# axiom_beta_sensor_cmv12000_v0_13_9164f85.net
KiCad netlist of a schematic drawn in EAGLE
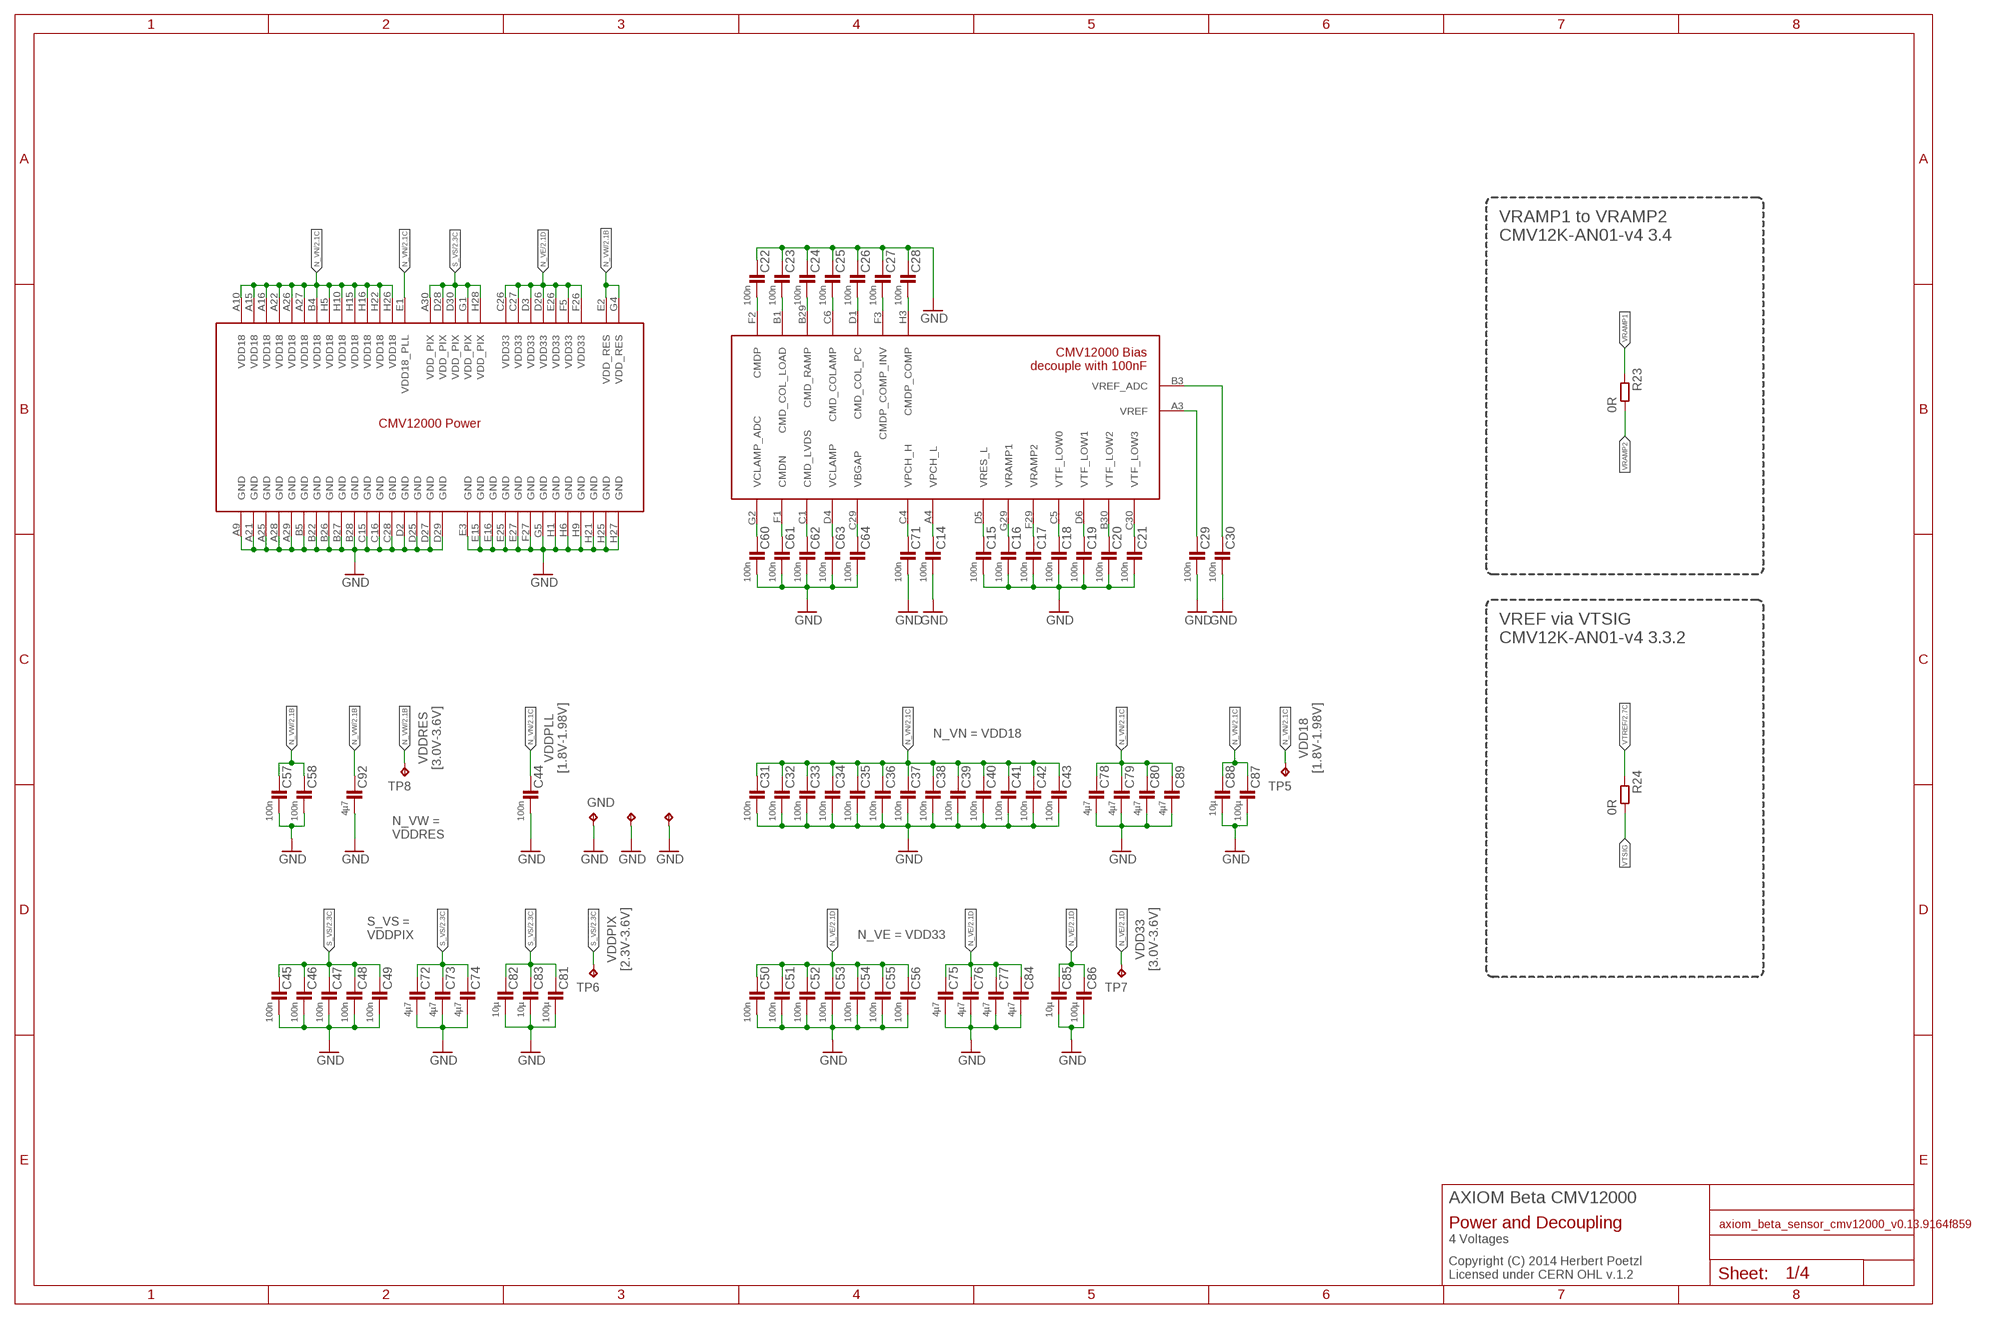
[diagram p0: schematic, sheet 1]
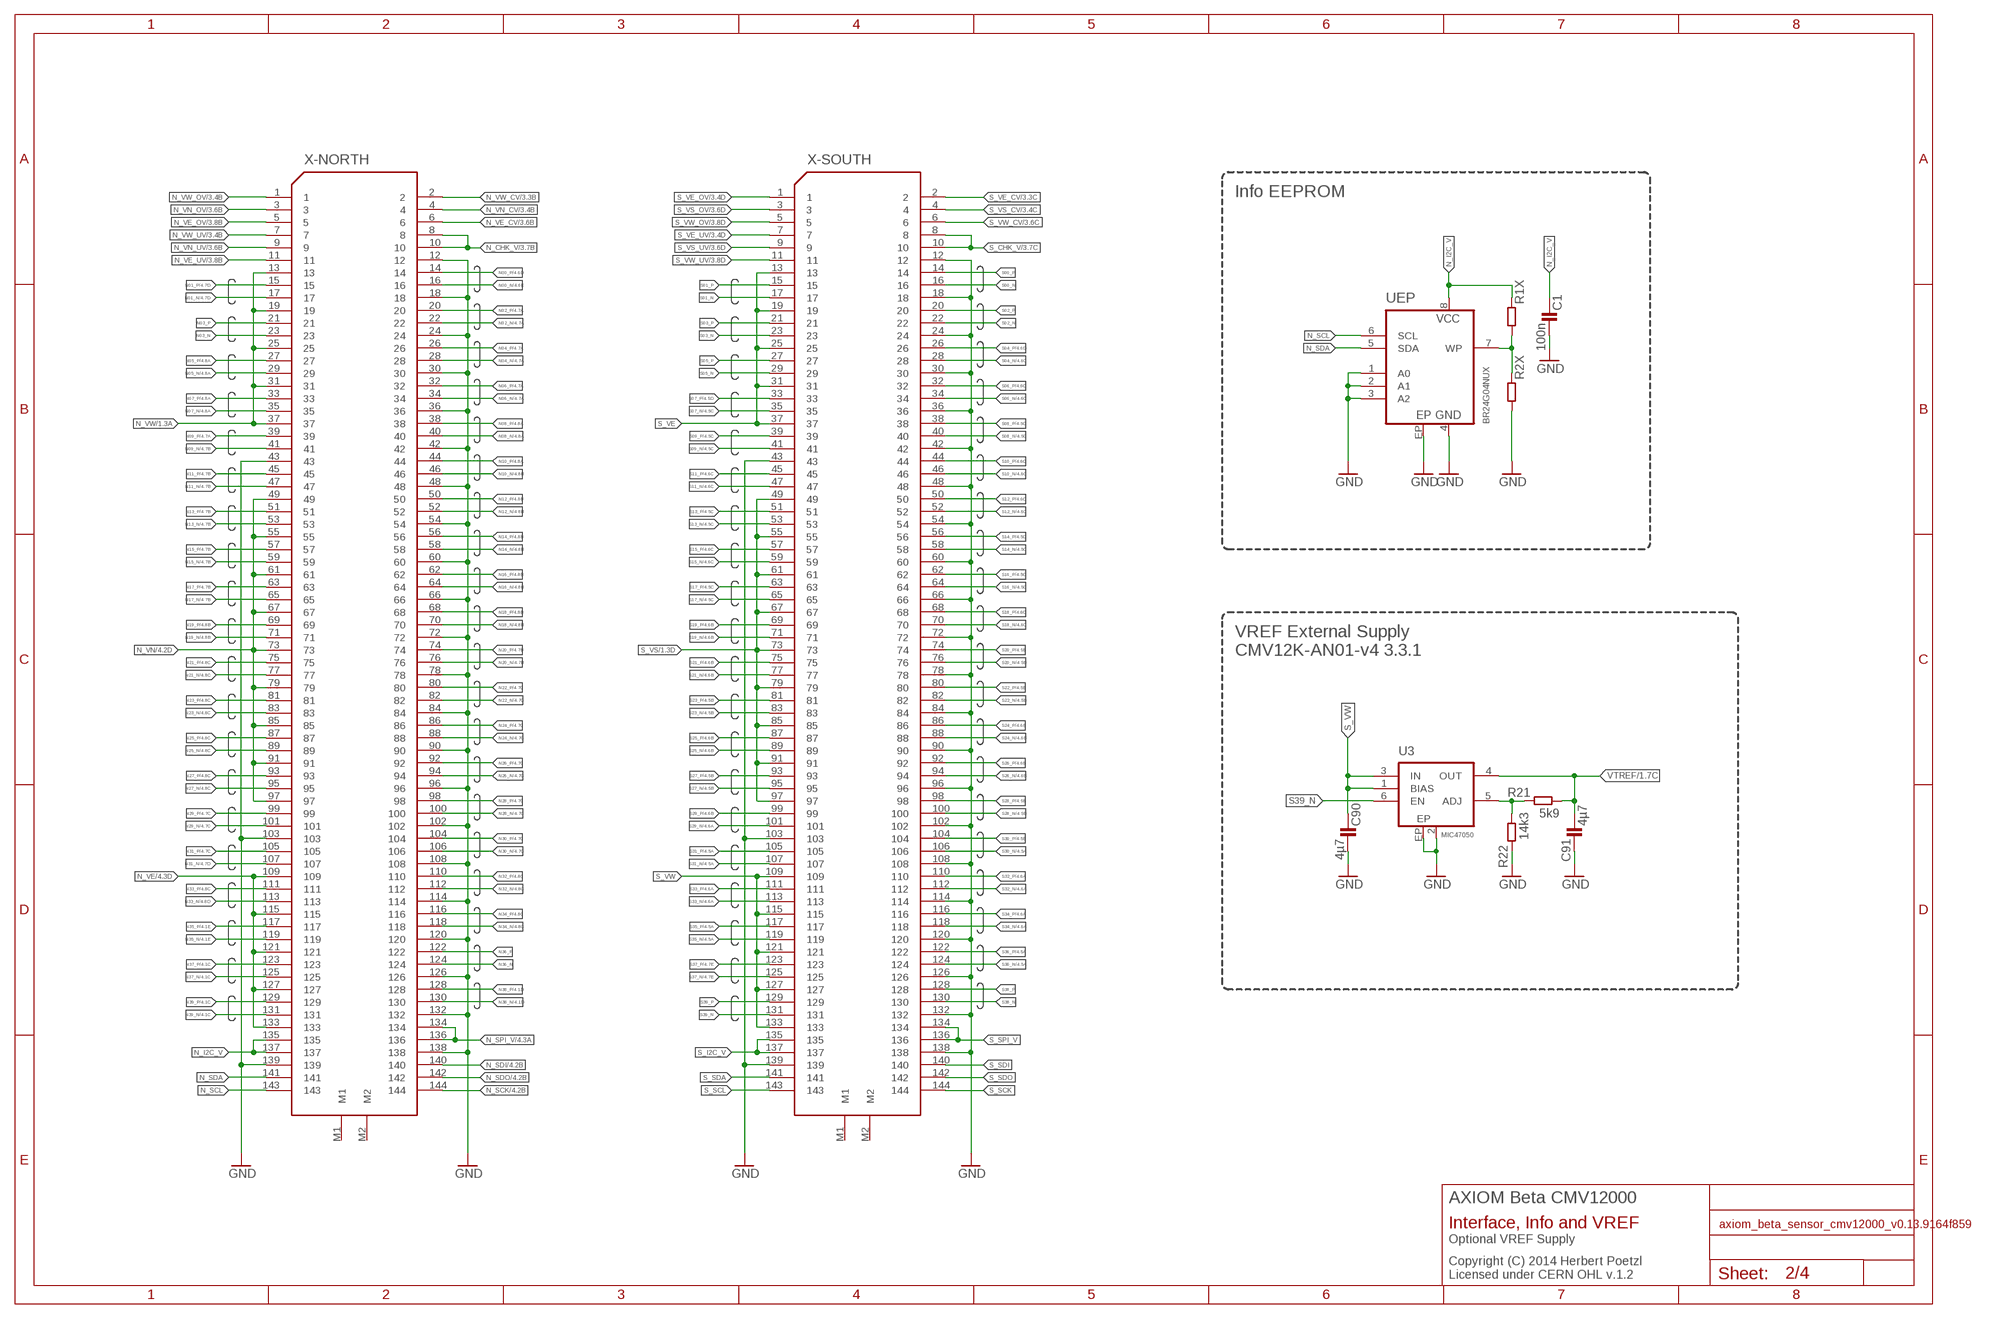
[diagram p1: schematic, sheet 2]
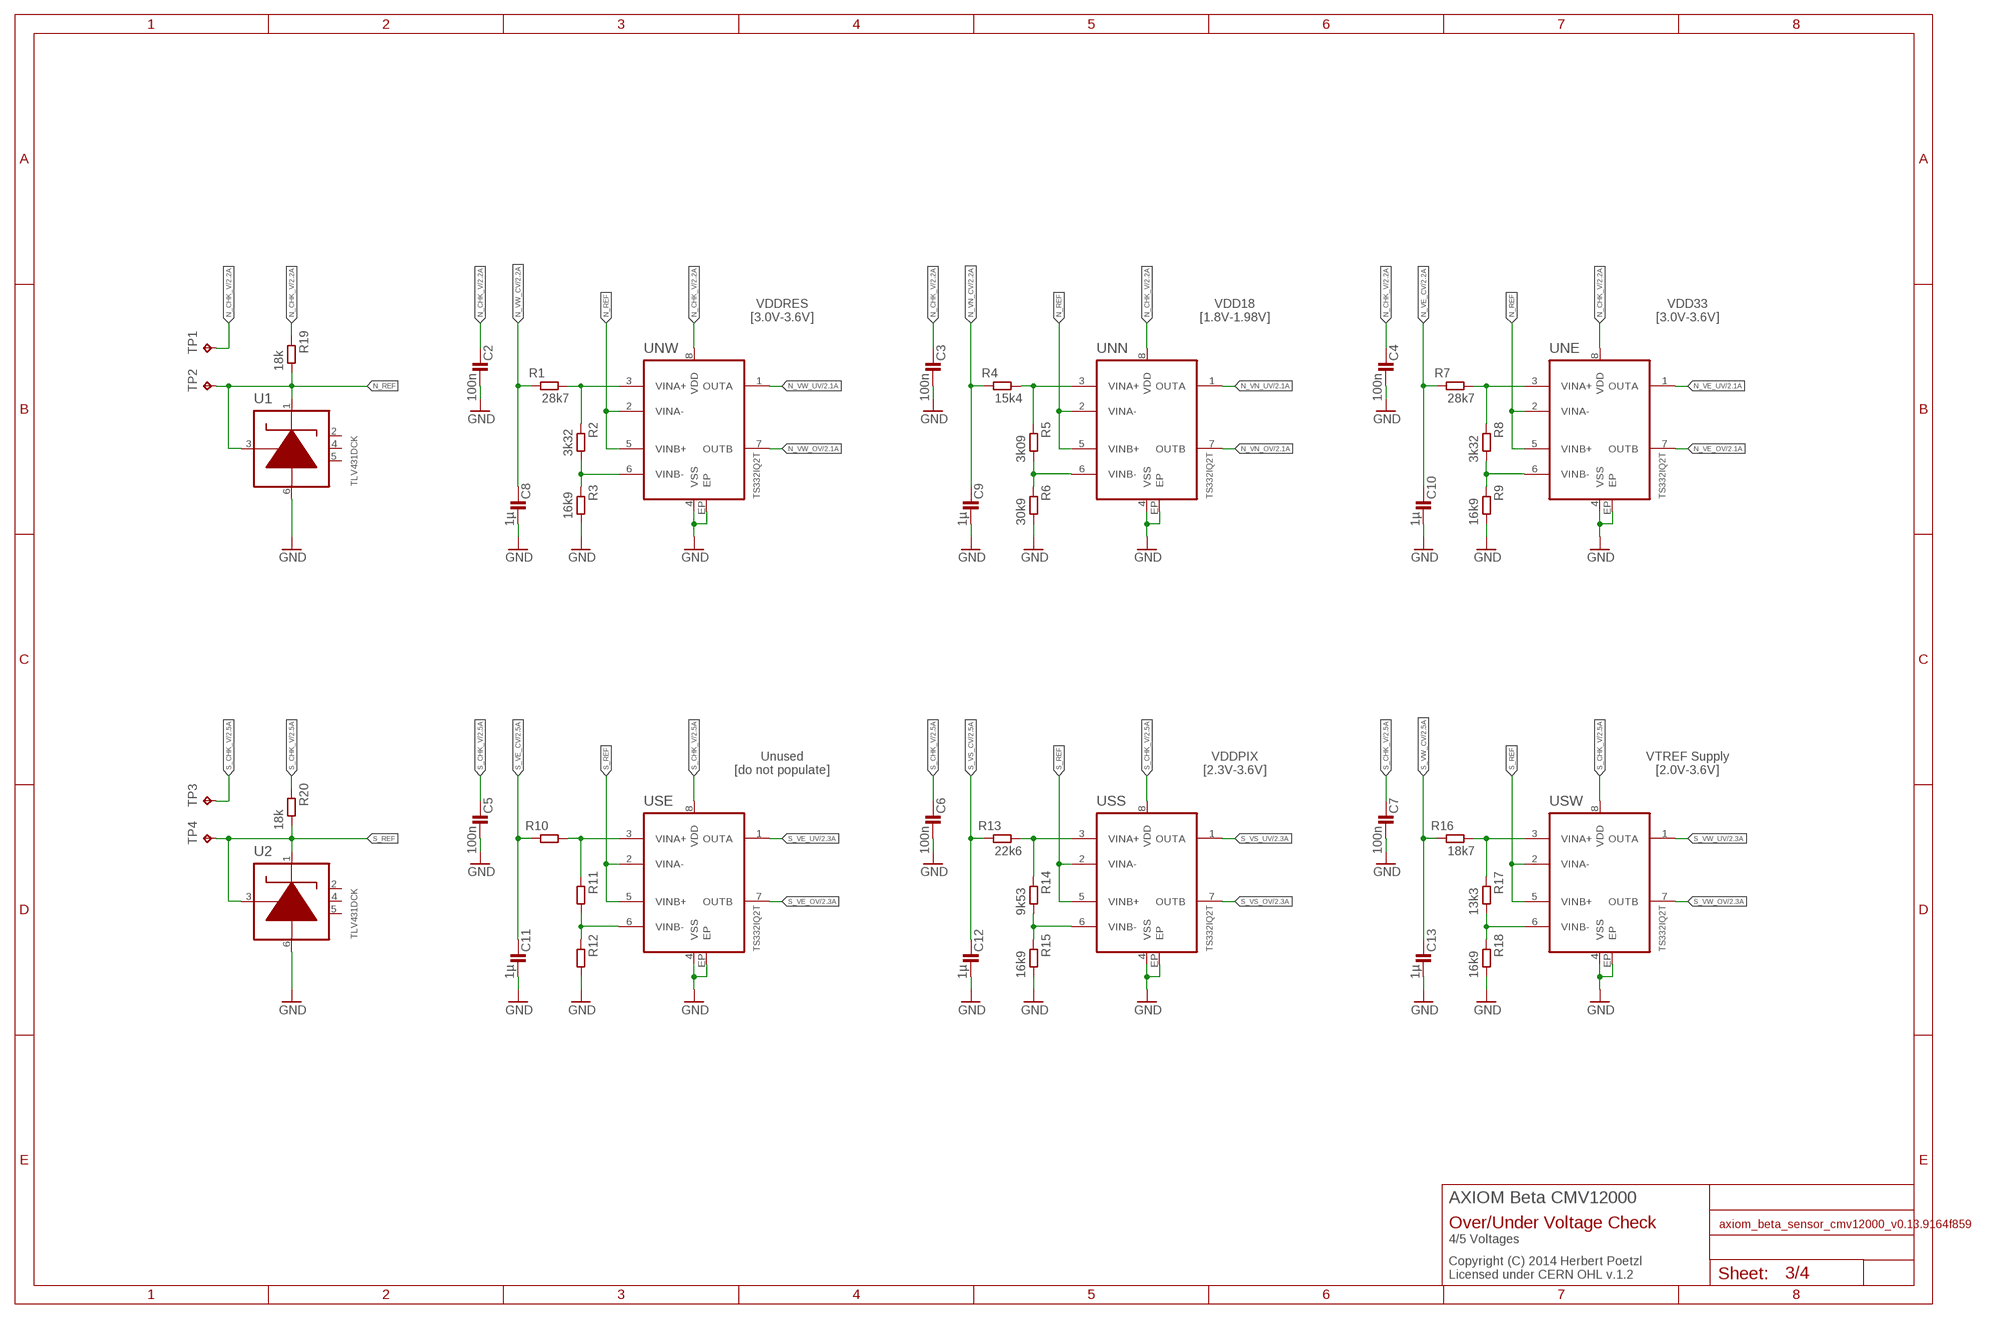
[diagram p2: schematic, sheet 3]
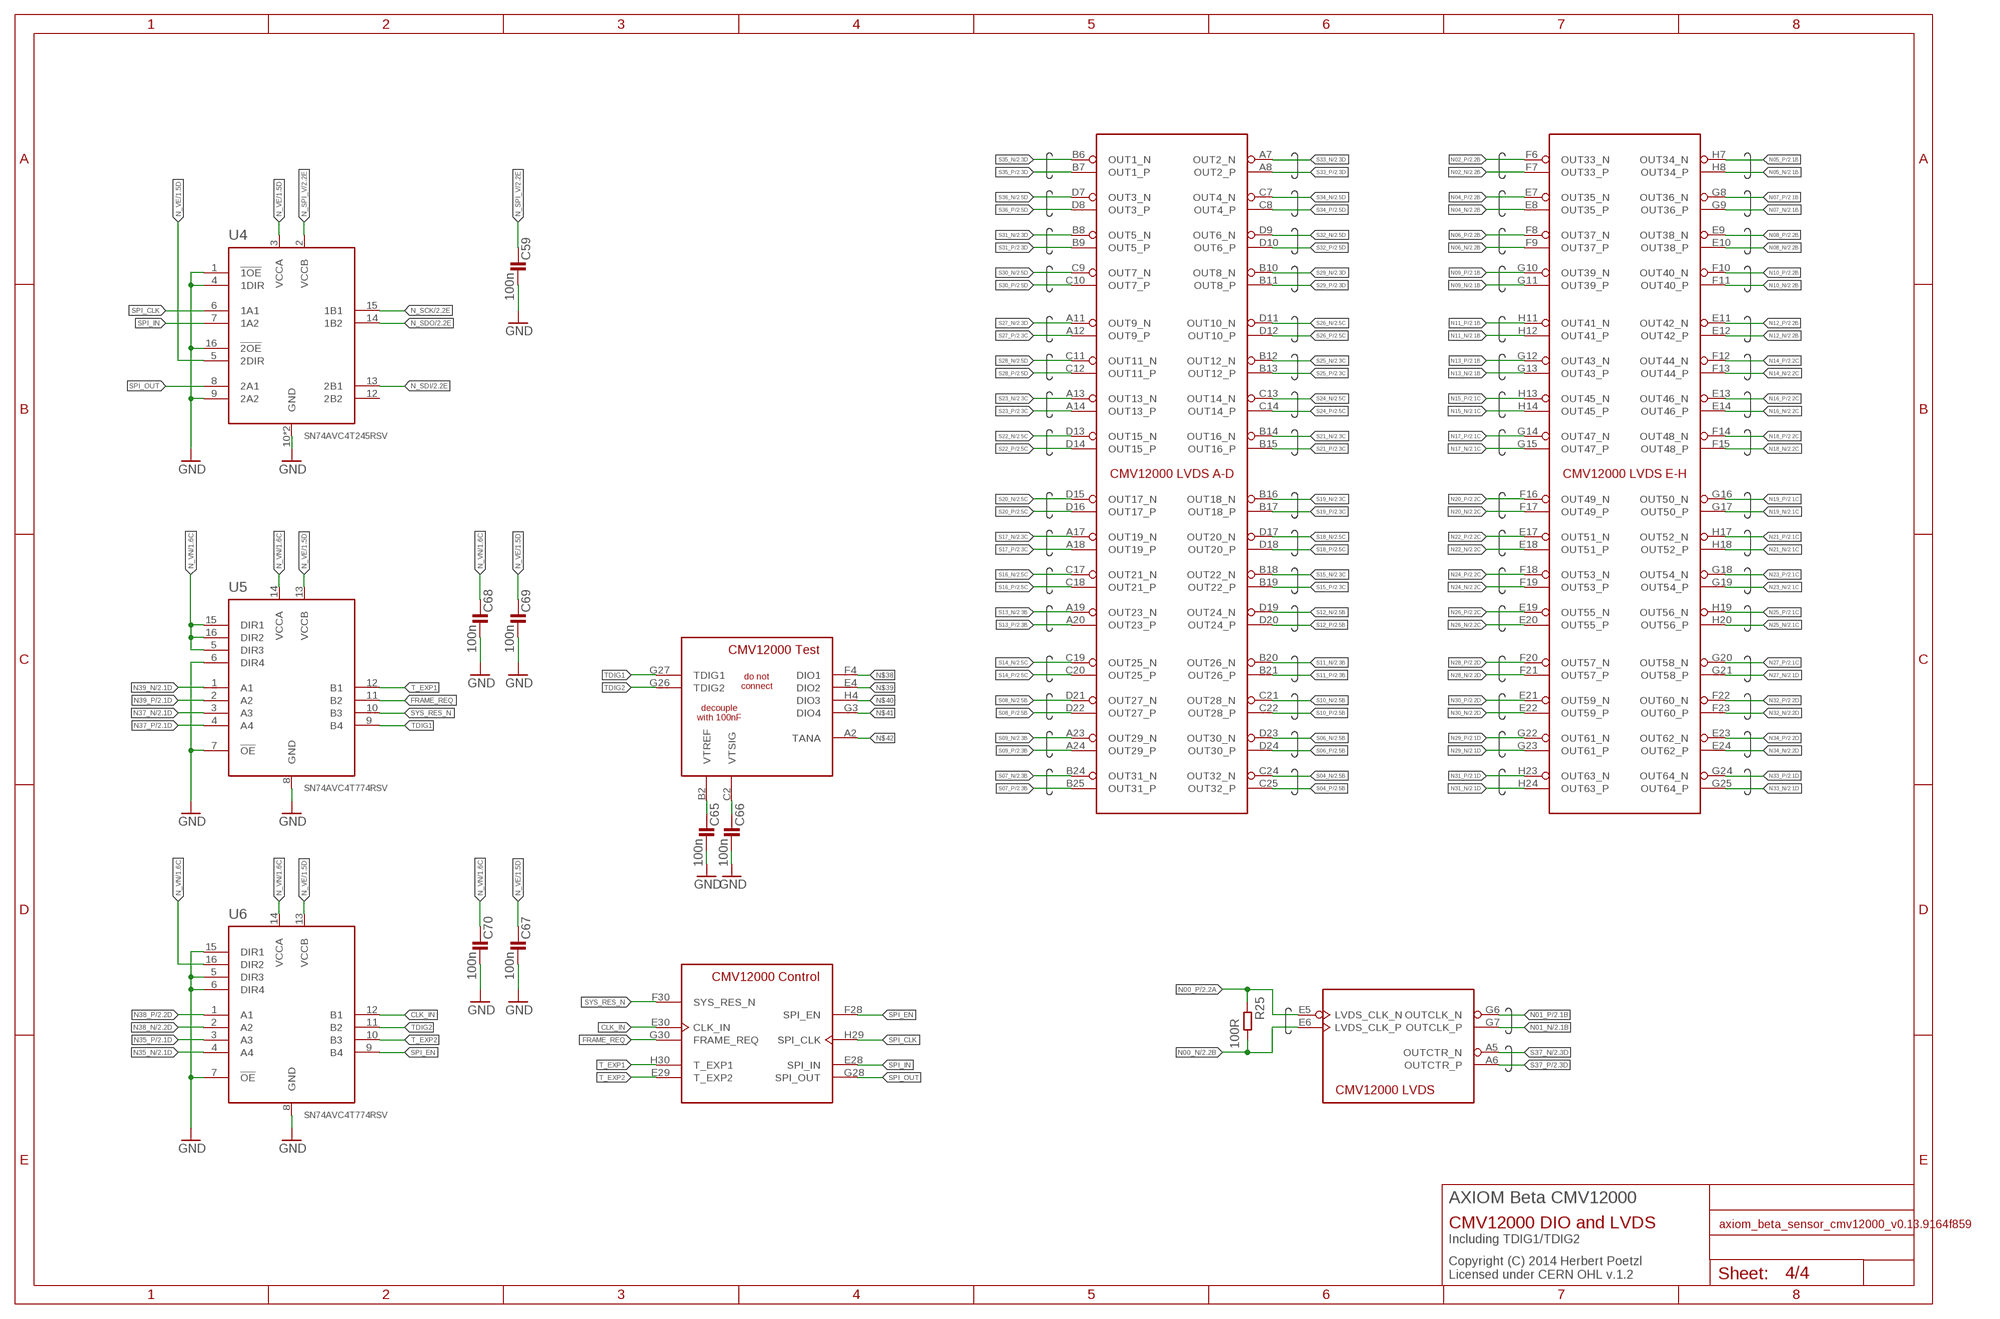
[diagram p3: schematic, sheet 4]

(export (version "E")
  (design (tool "Eeschema 10.0.6"))
  (components
    (comp (ref "C2")
      (value "100n")
      (footprint "eagle-import:0402-C")
      (libsource (lib "eagle-import") (part "C0402-C"))
    )
    (comp (ref "C3")
      (value "100n")
      (footprint "eagle-import:0402-C")
      (libsource (lib "eagle-import") (part "C0402-C"))
    )
    (comp (ref "C4")
      (value "100n")
      (footprint "eagle-import:0402-C")
      (libsource (lib "eagle-import") (part "C0402-C"))
    )
    (comp (ref "C5")
      (value "100n")
      (footprint "eagle-import:0402-C")
      (libsource (lib "eagle-import") (part "C0402-C"))
    )
    (comp (ref "C6")
      (value "100n")
      (footprint "eagle-import:0402-C")
      (libsource (lib "eagle-import") (part "C0402-C"))
    )
    (comp (ref "C7")
      (value "100n")
      (footprint "eagle-import:0402-C")
      (libsource (lib "eagle-import") (part "C0402-C"))
    )
    (comp (ref "C8")
      (value "1µ")
      (footprint "eagle-import:0402-C")
      (libsource (lib "eagle-import") (part "C0402-C"))
    )
    (comp (ref "C9")
      (value "1µ")
      (footprint "eagle-import:0402-C")
      (libsource (lib "eagle-import") (part "C0402-C"))
    )
    (comp (ref "C10")
      (value "1µ")
      (footprint "eagle-import:0402-C")
      (libsource (lib "eagle-import") (part "C0402-C"))
    )
    (comp (ref "C11")
      (value "1µ")
      (footprint "eagle-import:0402-C")
      (libsource (lib "eagle-import") (part "C0402-C"))
    )
    (comp (ref "C12")
      (value "1µ")
      (footprint "eagle-import:0402-C")
      (libsource (lib "eagle-import") (part "C0402-C"))
    )
    (comp (ref "C13")
      (value "1µ")
      (footprint "eagle-import:0402-C")
      (libsource (lib "eagle-import") (part "C0402-C"))
    )
    (comp (ref "R1")
      (value "28k7")
      (footprint "eagle-import:0402-C")
      (libsource (lib "eagle-import") (part "R0402-C"))
    )
    (comp (ref "R2")
      (value "3k32")
      (footprint "eagle-import:0402-C")
      (libsource (lib "eagle-import") (part "R0402-C"))
    )
    (comp (ref "R3")
      (value "16k9")
      (footprint "eagle-import:0402-C")
      (libsource (lib "eagle-import") (part "R0402-C"))
    )
    (comp (ref "R4")
      (value "15k4")
      (footprint "eagle-import:0402-C")
      (libsource (lib "eagle-import") (part "R0402-C"))
    )
    (comp (ref "R5")
      (value "3k09")
      (footprint "eagle-import:0402-C")
      (libsource (lib "eagle-import") (part "R0402-C"))
    )
    (comp (ref "R6")
      (value "30k9")
      (footprint "eagle-import:0402-C")
      (libsource (lib "eagle-import") (part "R0402-C"))
    )
    (comp (ref "R7")
      (value "28k7")
      (footprint "eagle-import:0402-C")
      (libsource (lib "eagle-import") (part "R0402-C"))
    )
    (comp (ref "R8")
      (value "3k32")
      (footprint "eagle-import:0402-C")
      (libsource (lib "eagle-import") (part "R0402-C"))
    )
    (comp (ref "R9")
      (value "16k9")
      (footprint "eagle-import:0402-C")
      (libsource (lib "eagle-import") (part "R0402-C"))
    )
    (comp (ref "R10")
      (value "R0402-C")
      (footprint "eagle-import:0402-C")
      (libsource (lib "eagle-import") (part "R0402-C"))
    )
    (comp (ref "R11")
      (value "R0402-C")
      (footprint "eagle-import:0402-C")
      (libsource (lib "eagle-import") (part "R0402-C"))
    )
    (comp (ref "R12")
      (value "R0402-C")
      (footprint "eagle-import:0402-C")
      (libsource (lib "eagle-import") (part "R0402-C"))
    )
    (comp (ref "R13")
      (value "22k6")
      (footprint "eagle-import:0402-C")
      (libsource (lib "eagle-import") (part "R0402-C"))
    )
    (comp (ref "R14")
      (value "9k53")
      (footprint "eagle-import:0402-C")
      (libsource (lib "eagle-import") (part "R0402-C"))
    )
    (comp (ref "R15")
      (value "16k9")
      (footprint "eagle-import:0402-C")
      (libsource (lib "eagle-import") (part "R0402-C"))
    )
    (comp (ref "R16")
      (value "18k7")
      (footprint "eagle-import:0402-C")
      (libsource (lib "eagle-import") (part "R0402-C"))
    )
    (comp (ref "R17")
      (value "13k3")
      (footprint "eagle-import:0402-C")
      (libsource (lib "eagle-import") (part "R0402-C"))
    )
    (comp (ref "R18")
      (value "16k9")
      (footprint "eagle-import:0402-C")
      (libsource (lib "eagle-import") (part "R0402-C"))
    )
    (comp (ref "R19")
      (value "18k")
      (footprint "eagle-import:0402-C")
      (libsource (lib "eagle-import") (part "R0402-C"))
    )
    (comp (ref "R20")
      (value "18k")
      (footprint "eagle-import:0402-C")
      (libsource (lib "eagle-import") (part "R0402-C"))
    )
    (comp (ref "TP1")
      (value "TPTP10R")
      (footprint "eagle-import:TP10R")
      (libsource (lib "eagle-import") (part "TPTP10R"))
    )
    (comp (ref "TP2")
      (value "TPTP10R")
      (footprint "eagle-import:TP10R")
      (libsource (lib "eagle-import") (part "TPTP10R"))
    )
    (comp (ref "TP3")
      (value "TPTP10R")
      (footprint "eagle-import:TP10R")
      (libsource (lib "eagle-import") (part "TPTP10R"))
    )
    (comp (ref "TP4")
      (value "TPTP10R")
      (footprint "eagle-import:TP10R")
      (libsource (lib "eagle-import") (part "TPTP10R"))
    )
    (comp (ref "U1")
      (value "TLV431DCK")
      (footprint "eagle-import:SOT65P210X110-6N")
      (libsource (lib "eagle-import") (part "TLV431DCK"))
    )
    (comp (ref "U2")
      (value "TLV431DCK")
      (footprint "eagle-import:SOT65P210X110-6N")
      (libsource (lib "eagle-import") (part "TLV431DCK"))
    )
    (comp (ref "UNE")
      (value "TS332IQ2T")
      (footprint "eagle-import:DFN200X200X100-9N")
      (libsource (lib "eagle-import") (part "TS332IQ2T"))
    )
    (comp (ref "UNN")
      (value "TS332IQ2T")
      (footprint "eagle-import:DFN200X200X100-9N")
      (libsource (lib "eagle-import") (part "TS332IQ2T"))
    )
    (comp (ref "UNW")
      (value "TS332IQ2T")
      (footprint "eagle-import:DFN200X200X100-9N")
      (libsource (lib "eagle-import") (part "TS332IQ2T"))
    )
    (comp (ref "USE")
      (value "TS332IQ2T")
      (footprint "eagle-import:DFN200X200X100-9N")
      (libsource (lib "eagle-import") (part "TS332IQ2T"))
    )
    (comp (ref "USS")
      (value "TS332IQ2T")
      (footprint "eagle-import:DFN200X200X100-9N")
      (libsource (lib "eagle-import") (part "TS332IQ2T"))
    )
    (comp (ref "USW")
      (value "TS332IQ2T")
      (footprint "eagle-import:DFN200X200X100-9N")
      (libsource (lib "eagle-import") (part "TS332IQ2T"))
    )
    (comp (ref "C59")
      (value "100n")
      (footprint "eagle-import:0402-C")
      (libsource (lib "eagle-import") (part "C0402-C"))
    )
    (comp (ref "C65")
      (value "100n")
      (footprint "eagle-import:0402-C")
      (libsource (lib "eagle-import") (part "C0402-C"))
    )
    (comp (ref "C66")
      (value "100n")
      (footprint "eagle-import:0402-C")
      (libsource (lib "eagle-import") (part "C0402-C"))
    )
    (comp (ref "C67")
      (value "100n")
      (footprint "eagle-import:0402-C")
      (libsource (lib "eagle-import") (part "C0402-C"))
    )
    (comp (ref "C68")
      (value "100n")
      (footprint "eagle-import:0402-C")
      (libsource (lib "eagle-import") (part "C0402-C"))
    )
    (comp (ref "C69")
      (value "100n")
      (footprint "eagle-import:0402-C")
      (libsource (lib "eagle-import") (part "C0402-C"))
    )
    (comp (ref "C70")
      (value "100n")
      (footprint "eagle-import:0402-C")
      (libsource (lib "eagle-import") (part "C0402-C"))
    )
    (comp (ref "R25")
      (value "100R")
      (footprint "eagle-import:0402-C")
      (libsource (lib "eagle-import") (part "R0402-C"))
    )
    (comp (ref "SENSOR")
      (value "CMV12000ANDON")
      (footprint "eagle-import:10-30-07-237-400T4")
      (libsource (lib "eagle-import") (part "CMV12000ANDON"))
    )
    (comp (ref "U4")
      (value "SN74AVC4T245RSV")
      (footprint "eagle-import:QFN40P185X265X55-16N")
      (libsource (lib "eagle-import") (part "SN74AVC4T245RSV"))
    )
    (comp (ref "U5")
      (value "SN74AVC4T774RSV")
      (footprint "eagle-import:QFN40P185X265X55-16N")
      (libsource (lib "eagle-import") (part "SN74AVC4T774RSV"))
    )
    (comp (ref "U6")
      (value "SN74AVC4T774RSV")
      (footprint "eagle-import:QFN40P185X265X55-16N")
      (libsource (lib "eagle-import") (part "SN74AVC4T774RSV"))
    )
    (comp (ref "C14")
      (value "100n")
      (footprint "eagle-import:0402-C")
      (libsource (lib "eagle-import") (part "C0402-C"))
    )
    (comp (ref "C15")
      (value "100n")
      (footprint "eagle-import:0402-C")
      (libsource (lib "eagle-import") (part "C0402-C"))
    )
    (comp (ref "C16")
      (value "100n")
      (footprint "eagle-import:0402-C")
      (libsource (lib "eagle-import") (part "C0402-C"))
    )
    (comp (ref "C17")
      (value "100n")
      (footprint "eagle-import:0402-C")
      (libsource (lib "eagle-import") (part "C0402-C"))
    )
    (comp (ref "C18")
      (value "100n")
      (footprint "eagle-import:0402-C")
      (libsource (lib "eagle-import") (part "C0402-C"))
    )
    (comp (ref "C19")
      (value "100n")
      (footprint "eagle-import:0402-C")
      (libsource (lib "eagle-import") (part "C0402-C"))
    )
    (comp (ref "C20")
      (value "100n")
      (footprint "eagle-import:0402-C")
      (libsource (lib "eagle-import") (part "C0402-C"))
    )
    (comp (ref "C21")
      (value "100n")
      (footprint "eagle-import:0402-C")
      (libsource (lib "eagle-import") (part "C0402-C"))
    )
    (comp (ref "C22")
      (value "100n")
      (footprint "eagle-import:0402-C")
      (libsource (lib "eagle-import") (part "C0402-C"))
    )
    (comp (ref "C23")
      (value "100n")
      (footprint "eagle-import:0402-C")
      (libsource (lib "eagle-import") (part "C0402-C"))
    )
    (comp (ref "C24")
      (value "100n")
      (footprint "eagle-import:0402-C")
      (libsource (lib "eagle-import") (part "C0402-C"))
    )
    (comp (ref "C25")
      (value "100n")
      (footprint "eagle-import:0402-C")
      (libsource (lib "eagle-import") (part "C0402-C"))
    )
    (comp (ref "C26")
      (value "100n")
      (footprint "eagle-import:0402-C")
      (libsource (lib "eagle-import") (part "C0402-C"))
    )
    (comp (ref "C27")
      (value "100n")
      (footprint "eagle-import:0402-C")
      (libsource (lib "eagle-import") (part "C0402-C"))
    )
    (comp (ref "C28")
      (value "100n")
      (footprint "eagle-import:0402-C")
      (libsource (lib "eagle-import") (part "C0402-C"))
    )
    (comp (ref "C29")
      (value "100n")
      (footprint "eagle-import:0402-C")
      (libsource (lib "eagle-import") (part "C0402-C"))
    )
    (comp (ref "C30")
      (value "100n")
      (footprint "eagle-import:0402-C")
      (libsource (lib "eagle-import") (part "C0402-C"))
    )
    (comp (ref "C31")
      (value "100n")
      (footprint "eagle-import:0402-C")
      (libsource (lib "eagle-import") (part "C0402-C"))
    )
    (comp (ref "C32")
      (value "100n")
      (footprint "eagle-import:0402-C")
      (libsource (lib "eagle-import") (part "C0402-C"))
    )
    (comp (ref "C33")
      (value "100n")
      (footprint "eagle-import:0402-C")
      (libsource (lib "eagle-import") (part "C0402-C"))
    )
    (comp (ref "C34")
      (value "100n")
      (footprint "eagle-import:0402-C")
      (libsource (lib "eagle-import") (part "C0402-C"))
    )
    (comp (ref "C35")
      (value "100n")
      (footprint "eagle-import:0402-C")
      (libsource (lib "eagle-import") (part "C0402-C"))
    )
    (comp (ref "C36")
      (value "100n")
      (footprint "eagle-import:0402-C")
      (libsource (lib "eagle-import") (part "C0402-C"))
    )
    (comp (ref "C37")
      (value "100n")
      (footprint "eagle-import:0402-C")
      (libsource (lib "eagle-import") (part "C0402-C"))
    )
    (comp (ref "C38")
      (value "100n")
      (footprint "eagle-import:0402-C")
      (libsource (lib "eagle-import") (part "C0402-C"))
    )
    (comp (ref "C39")
      (value "100n")
      (footprint "eagle-import:0402-C")
      (libsource (lib "eagle-import") (part "C0402-C"))
    )
    (comp (ref "C40")
      (value "100n")
      (footprint "eagle-import:0402-C")
      (libsource (lib "eagle-import") (part "C0402-C"))
    )
    (comp (ref "C41")
      (value "100n")
      (footprint "eagle-import:0402-C")
      (libsource (lib "eagle-import") (part "C0402-C"))
    )
    (comp (ref "C42")
      (value "100n")
      (footprint "eagle-import:0402-C")
      (libsource (lib "eagle-import") (part "C0402-C"))
    )
    (comp (ref "C43")
      (value "100n")
      (footprint "eagle-import:0402-C")
      (libsource (lib "eagle-import") (part "C0402-C"))
    )
    (comp (ref "C44")
      (value "100n")
      (footprint "eagle-import:0402-C")
      (libsource (lib "eagle-import") (part "C0402-C"))
    )
    (comp (ref "C45")
      (value "100n")
      (footprint "eagle-import:0402-C")
      (libsource (lib "eagle-import") (part "C0402-C"))
    )
    (comp (ref "C46")
      (value "100n")
      (footprint "eagle-import:0402-C")
      (libsource (lib "eagle-import") (part "C0402-C"))
    )
    (comp (ref "C47")
      (value "100n")
      (footprint "eagle-import:0402-C")
      (libsource (lib "eagle-import") (part "C0402-C"))
    )
    (comp (ref "C48")
      (value "100n")
      (footprint "eagle-import:0402-C")
      (libsource (lib "eagle-import") (part "C0402-C"))
    )
    (comp (ref "C49")
      (value "100n")
      (footprint "eagle-import:0402-C")
      (libsource (lib "eagle-import") (part "C0402-C"))
    )
    (comp (ref "C50")
      (value "100n")
      (footprint "eagle-import:0402-C")
      (libsource (lib "eagle-import") (part "C0402-C"))
    )
    (comp (ref "C51")
      (value "100n")
      (footprint "eagle-import:0402-C")
      (libsource (lib "eagle-import") (part "C0402-C"))
    )
    (comp (ref "C52")
      (value "100n")
      (footprint "eagle-import:0402-C")
      (libsource (lib "eagle-import") (part "C0402-C"))
    )
    (comp (ref "C53")
      (value "100n")
      (footprint "eagle-import:0402-C")
      (libsource (lib "eagle-import") (part "C0402-C"))
    )
    (comp (ref "C54")
      (value "100n")
      (footprint "eagle-import:0402-C")
      (libsource (lib "eagle-import") (part "C0402-C"))
    )
    (comp (ref "C55")
      (value "100n")
      (footprint "eagle-import:0402-C")
      (libsource (lib "eagle-import") (part "C0402-C"))
    )
    (comp (ref "C56")
      (value "100n")
      (footprint "eagle-import:0402-C")
      (libsource (lib "eagle-import") (part "C0402-C"))
    )
    (comp (ref "C57")
      (value "100n")
      (footprint "eagle-import:0402-C")
      (libsource (lib "eagle-import") (part "C0402-C"))
    )
    (comp (ref "C58")
      (value "100n")
      (footprint "eagle-import:0402-C")
      (libsource (lib "eagle-import") (part "C0402-C"))
    )
    (comp (ref "C60")
      (value "100n")
      (footprint "eagle-import:0402-C")
      (libsource (lib "eagle-import") (part "C0402-C"))
    )
    (comp (ref "C61")
      (value "100n")
      (footprint "eagle-import:0402-C")
      (libsource (lib "eagle-import") (part "C0402-C"))
    )
    (comp (ref "C62")
      (value "100n")
      (footprint "eagle-import:0402-C")
      (libsource (lib "eagle-import") (part "C0402-C"))
    )
    (comp (ref "C63")
      (value "100n")
      (footprint "eagle-import:0402-C")
      (libsource (lib "eagle-import") (part "C0402-C"))
    )
    (comp (ref "C64")
      (value "100n")
      (footprint "eagle-import:0402-C")
      (libsource (lib "eagle-import") (part "C0402-C"))
    )
    (comp (ref "C71")
      (value "100n")
      (footprint "eagle-import:0402-C")
      (libsource (lib "eagle-import") (part "C0402-C"))
    )
    (comp (ref "C72")
      (value "4µ7")
      (footprint "eagle-import:0402-B")
      (libsource (lib "eagle-import") (part "C0402-B"))
    )
    (comp (ref "C73")
      (value "4µ7")
      (footprint "eagle-import:0402-C")
      (libsource (lib "eagle-import") (part "C0402-C"))
    )
    (comp (ref "C74")
      (value "4µ7")
      (footprint "eagle-import:0402-C")
      (libsource (lib "eagle-import") (part "C0402-C"))
    )
    (comp (ref "C75")
      (value "4µ7")
      (footprint "eagle-import:0402-C")
      (libsource (lib "eagle-import") (part "C0402-C"))
    )
    (comp (ref "C76")
      (value "4µ7")
      (footprint "eagle-import:0402-C")
      (libsource (lib "eagle-import") (part "C0402-C"))
    )
    (comp (ref "C77")
      (value "4µ7")
      (footprint "eagle-import:0402-B")
      (libsource (lib "eagle-import") (part "C0402-B"))
    )
    (comp (ref "C78")
      (value "4µ7")
      (footprint "eagle-import:0402-B")
      (libsource (lib "eagle-import") (part "C0402-B"))
    )
    (comp (ref "C79")
      (value "4µ7")
      (footprint "eagle-import:0402-C")
      (libsource (lib "eagle-import") (part "C0402-C"))
    )
    (comp (ref "C80")
      (value "4µ7")
      (footprint "eagle-import:0402-C")
      (libsource (lib "eagle-import") (part "C0402-C"))
    )
    (comp (ref "C81")
      (value "100µ")
      (footprint "eagle-import:1206-B")
      (libsource (lib "eagle-import") (part "C1206-B"))
    )
    (comp (ref "C82")
      (value "10µ")
      (footprint "eagle-import:0603-C")
      (libsource (lib "eagle-import") (part "C0603-C"))
    )
    (comp (ref "C83")
      (value "10µ")
      (footprint "eagle-import:0603-C")
      (libsource (lib "eagle-import") (part "C0603-C"))
    )
    (comp (ref "C84")
      (value "4µ7")
      (footprint "eagle-import:0402-C")
      (libsource (lib "eagle-import") (part "C0402-C"))
    )
    (comp (ref "C85")
      (value "10µ")
      (footprint "eagle-import:0603-C")
      (libsource (lib "eagle-import") (part "C0603-C"))
    )
    (comp (ref "C86")
      (value "100µ")
      (footprint "eagle-import:1206-B")
      (libsource (lib "eagle-import") (part "C1206-B"))
    )
    (comp (ref "C87")
      (value "100µ")
      (footprint "eagle-import:1206-B")
      (libsource (lib "eagle-import") (part "C1206-B"))
    )
    (comp (ref "C88")
      (value "10µ")
      (footprint "eagle-import:0603-C")
      (libsource (lib "eagle-import") (part "C0603-C"))
    )
    (comp (ref "C89")
      (value "4µ7")
      (footprint "eagle-import:0402-C")
      (libsource (lib "eagle-import") (part "C0402-C"))
    )
    (comp (ref "C92")
      (value "4µ7")
      (footprint "eagle-import:0402-C")
      (libsource (lib "eagle-import") (part "C0402-C"))
    )
    (comp (ref "GND")
      (value "TPTP10R")
      (footprint "eagle-import:TP10R")
      (libsource (lib "eagle-import") (part "TPTP10R"))
    )
    (comp (ref "GND75")
      (value "TPTP10R")
      (footprint "eagle-import:TP10R")
      (libsource (lib "eagle-import") (part "TPTP10R"))
    )
    (comp (ref "GND77")
      (value "TPTP10R")
      (footprint "eagle-import:TP10R")
      (libsource (lib "eagle-import") (part "TPTP10R"))
    )
    (comp (ref "R23")
      (value "0R")
      (footprint "eagle-import:0402-C")
      (libsource (lib "eagle-import") (part "R0402-C"))
    )
    (comp (ref "R24")
      (value "0R")
      (footprint "eagle-import:0402-C")
      (libsource (lib "eagle-import") (part "R0402-C"))
    )
    (comp (ref "TP5")
      (value "TPTP10R")
      (footprint "eagle-import:TP10R")
      (libsource (lib "eagle-import") (part "TPTP10R"))
    )
    (comp (ref "TP6")
      (value "TPTP10R")
      (footprint "eagle-import:TP10R")
      (libsource (lib "eagle-import") (part "TPTP10R"))
    )
    (comp (ref "TP7")
      (value "TPTP10R")
      (footprint "eagle-import:TP10R")
      (libsource (lib "eagle-import") (part "TPTP10R"))
    )
    (comp (ref "TP8")
      (value "TPTP10R")
      (footprint "eagle-import:TP10R")
      (libsource (lib "eagle-import") (part "TPTP10R"))
    )
    (comp (ref "C1")
      (value "100n")
      (footprint "eagle-import:0402-C")
      (libsource (lib "eagle-import") (part "C0402-C"))
    )
    (comp (ref "C90")
      (value "4µ7")
      (footprint "eagle-import:0402-C")
      (libsource (lib "eagle-import") (part "C0402-C"))
    )
    (comp (ref "C91")
      (value "4µ7")
      (footprint "eagle-import:0402-C")
      (libsource (lib "eagle-import") (part "C0402-C"))
    )
    (comp (ref "R1X")
      (value "R0402-C")
      (footprint "eagle-import:0402-C")
      (libsource (lib "eagle-import") (part "R0402-C"))
    )
    (comp (ref "R2X")
      (value "R0402-C")
      (footprint "eagle-import:0402-C")
      (libsource (lib "eagle-import") (part "R0402-C"))
    )
    (comp (ref "R21")
      (value "5k9")
      (footprint "eagle-import:0402-C")
      (libsource (lib "eagle-import") (part "R0402-C"))
    )
    (comp (ref "R22")
      (value "14k3")
      (footprint "eagle-import:0402-C")
      (libsource (lib "eagle-import") (part "R0402-C"))
    )
    (comp (ref "U3")
      (value "MIC47050")
      (footprint "eagle-import:MLF-6")
      (libsource (lib "eagle-import") (part "MIC47050-ADJ"))
    )
    (comp (ref "UEP")
      (value "BR24G04NUX")
      (footprint "eagle-import:DFN200X300X100-9N")
      (libsource (lib "eagle-import") (part "BR24G04NUX"))
    )
    (comp (ref "X-NORTH")
      (value "FX10-144P")
      (footprint "eagle-import:FX10A-144P")
      (libsource (lib "eagle-import") (part "FX10-144P"))
    )
    (comp (ref "X-SOUTH")
      (value "FX10-144P")
      (footprint "eagle-import:FX10A-144P")
      (libsource (lib "eagle-import") (part "FX10-144P"))
    )
  )
  (nets
    (net (code "1") (name "CLK_IN") (class "Default")
      (node (ref "SENSOR") (pin "E30") (pinfunction "CLK_IN_E30") (pintype "input"))
      (node (ref "U6") (pin "12") (pinfunction "B1_12") (pintype "bidirectional"))
    )
    (net (code "2") (name "FRAME_REQ") (class "Default")
      (node (ref "SENSOR") (pin "G30") (pinfunction "FRAME_REQ_G30") (pintype "input"))
      (node (ref "U5") (pin "11") (pinfunction "B2_11") (pintype "bidirectional"))
    )
    (net (code "3") (name "GND") (class "Default")
      (node (ref "C1") (pin "2") (pinfunction "2_2") (pintype "passive"))
      (node (ref "C10") (pin "2") (pinfunction "2_2") (pintype "passive"))
      (node (ref "C11") (pin "2") (pinfunction "2_2") (pintype "passive"))
      (node (ref "C12") (pin "2") (pinfunction "2_2") (pintype "passive"))
      (node (ref "C13") (pin "2") (pinfunction "2_2") (pintype "passive"))
      (node (ref "C14") (pin "2") (pinfunction "2_2") (pintype "passive"))
      (node (ref "C15") (pin "2") (pinfunction "2_2") (pintype "passive"))
      (node (ref "C16") (pin "2") (pinfunction "2_2") (pintype "passive"))
      (node (ref "C17") (pin "2") (pinfunction "2_2") (pintype "passive"))
      (node (ref "C18") (pin "2") (pinfunction "2_2") (pintype "passive"))
      (node (ref "C19") (pin "2") (pinfunction "2_2") (pintype "passive"))
      (node (ref "C2") (pin "2") (pinfunction "2_2") (pintype "passive"))
      (node (ref "C20") (pin "2") (pinfunction "2_2") (pintype "passive"))
      (node (ref "C21") (pin "2") (pinfunction "2_2") (pintype "passive"))
      (node (ref "C22") (pin "1") (pinfunction "1_1") (pintype "passive"))
      (node (ref "C23") (pin "1") (pinfunction "1_1") (pintype "passive"))
      (node (ref "C24") (pin "1") (pinfunction "1_1") (pintype "passive"))
      (node (ref "C25") (pin "1") (pinfunction "1_1") (pintype "passive"))
      (node (ref "C26") (pin "1") (pinfunction "1_1") (pintype "passive"))
      (node (ref "C27") (pin "1") (pinfunction "1_1") (pintype "passive"))
      (node (ref "C28") (pin "1") (pinfunction "1_1") (pintype "passive"))
      (node (ref "C29") (pin "2") (pinfunction "2_2") (pintype "passive"))
      (node (ref "C3") (pin "2") (pinfunction "2_2") (pintype "passive"))
      (node (ref "C30") (pin "2") (pinfunction "2_2") (pintype "passive"))
      (node (ref "C31") (pin "2") (pinfunction "2_2") (pintype "passive"))
      (node (ref "C32") (pin "2") (pinfunction "2_2") (pintype "passive"))
      (node (ref "C33") (pin "2") (pinfunction "2_2") (pintype "passive"))
      (node (ref "C34") (pin "2") (pinfunction "2_2") (pintype "passive"))
      (node (ref "C35") (pin "2") (pinfunction "2_2") (pintype "passive"))
      (node (ref "C36") (pin "2") (pinfunction "2_2") (pintype "passive"))
      (node (ref "C37") (pin "2") (pinfunction "2_2") (pintype "passive"))
      (node (ref "C38") (pin "2") (pinfunction "2_2") (pintype "passive"))
      (node (ref "C39") (pin "2") (pinfunction "2_2") (pintype "passive"))
      (node (ref "C4") (pin "2") (pinfunction "2_2") (pintype "passive"))
      (node (ref "C40") (pin "2") (pinfunction "2_2") (pintype "passive"))
      (node (ref "C41") (pin "2") (pinfunction "2_2") (pintype "passive"))
      (node (ref "C42") (pin "2") (pinfunction "2_2") (pintype "passive"))
      (node (ref "C43") (pin "2") (pinfunction "2_2") (pintype "passive"))
      (node (ref "C44") (pin "2") (pinfunction "2_2") (pintype "passive"))
      (node (ref "C45") (pin "2") (pinfunction "2_2") (pintype "passive"))
      (node (ref "C46") (pin "2") (pinfunction "2_2") (pintype "passive"))
      (node (ref "C47") (pin "2") (pinfunction "2_2") (pintype "passive"))
      (node (ref "C48") (pin "2") (pinfunction "2_2") (pintype "passive"))
      (node (ref "C49") (pin "2") (pinfunction "2_2") (pintype "passive"))
      (node (ref "C5") (pin "2") (pinfunction "2_2") (pintype "passive"))
      (node (ref "C50") (pin "2") (pinfunction "2_2") (pintype "passive"))
      (node (ref "C51") (pin "2") (pinfunction "2_2") (pintype "passive"))
      (node (ref "C52") (pin "2") (pinfunction "2_2") (pintype "passive"))
      (node (ref "C53") (pin "2") (pinfunction "2_2") (pintype "passive"))
      (node (ref "C54") (pin "2") (pinfunction "2_2") (pintype "passive"))
      (node (ref "C55") (pin "2") (pinfunction "2_2") (pintype "passive"))
      (node (ref "C56") (pin "2") (pinfunction "2_2") (pintype "passive"))
      (node (ref "C57") (pin "2") (pinfunction "2_2") (pintype "passive"))
      (node (ref "C58") (pin "2") (pinfunction "2_2") (pintype "passive"))
      (node (ref "C59") (pin "2") (pinfunction "2_2") (pintype "passive"))
      (node (ref "C6") (pin "2") (pinfunction "2_2") (pintype "passive"))
      (node (ref "C60") (pin "2") (pinfunction "2_2") (pintype "passive"))
      (node (ref "C61") (pin "2") (pinfunction "2_2") (pintype "passive"))
      (node (ref "C62") (pin "2") (pinfunction "2_2") (pintype "passive"))
      (node (ref "C63") (pin "2") (pinfunction "2_2") (pintype "passive"))
      (node (ref "C64") (pin "2") (pinfunction "2_2") (pintype "passive"))
      (node (ref "C65") (pin "2") (pinfunction "2_2") (pintype "passive"))
      (node (ref "C66") (pin "2") (pinfunction "2_2") (pintype "passive"))
      (node (ref "C67") (pin "2") (pinfunction "2_2") (pintype "passive"))
      (node (ref "C68") (pin "2") (pinfunction "2_2") (pintype "passive"))
      (node (ref "C69") (pin "2") (pinfunction "2_2") (pintype "passive"))
      (node (ref "C7") (pin "2") (pinfunction "2_2") (pintype "passive"))
      (node (ref "C70") (pin "2") (pinfunction "2_2") (pintype "passive"))
      (node (ref "C71") (pin "2") (pinfunction "2_2") (pintype "passive"))
      (node (ref "C72") (pin "2") (pinfunction "2_2") (pintype "passive"))
      (node (ref "C73") (pin "2") (pinfunction "2_2") (pintype "passive"))
      (node (ref "C74") (pin "2") (pinfunction "2_2") (pintype "passive"))
      (node (ref "C75") (pin "2") (pinfunction "2_2") (pintype "passive"))
      (node (ref "C76") (pin "2") (pinfunction "2_2") (pintype "passive"))
      (node (ref "C77") (pin "2") (pinfunction "2_2") (pintype "passive"))
      (node (ref "C78") (pin "2") (pinfunction "2_2") (pintype "passive"))
      (node (ref "C79") (pin "2") (pinfunction "2_2") (pintype "passive"))
      (node (ref "C8") (pin "2") (pinfunction "2_2") (pintype "passive"))
      (node (ref "C80") (pin "2") (pinfunction "2_2") (pintype "passive"))
      (node (ref "C81") (pin "2") (pinfunction "2_2") (pintype "passive"))
      (node (ref "C82") (pin "2") (pinfunction "2_2") (pintype "passive"))
      (node (ref "C83") (pin "2") (pinfunction "2_2") (pintype "passive"))
      (node (ref "C84") (pin "2") (pinfunction "2_2") (pintype "passive"))
      (node (ref "C85") (pin "2") (pinfunction "2_2") (pintype "passive"))
      (node (ref "C86") (pin "2") (pinfunction "2_2") (pintype "passive"))
      (node (ref "C87") (pin "2") (pinfunction "2_2") (pintype "passive"))
      (node (ref "C88") (pin "2") (pinfunction "2_2") (pintype "passive"))
      (node (ref "C89") (pin "2") (pinfunction "2_2") (pintype "passive"))
      (node (ref "C9") (pin "2") (pinfunction "2_2") (pintype "passive"))
      (node (ref "C90") (pin "2") (pinfunction "2_2") (pintype "passive"))
      (node (ref "C91") (pin "1") (pinfunction "1_1") (pintype "passive"))
      (node (ref "C92") (pin "2") (pinfunction "2_2") (pintype "passive"))
      (node (ref "GND") (pin "TP") (pinfunction "TP_TP") (pintype "input"))
      (node (ref "GND75") (pin "TP") (pinfunction "TP_TP") (pintype "input"))
      (node (ref "GND77") (pin "TP") (pinfunction "TP_TP") (pintype "input"))
      (node (ref "R12") (pin "2") (pinfunction "2_2") (pintype "passive"))
      (node (ref "R15") (pin "2") (pinfunction "2_2") (pintype "passive"))
      (node (ref "R18") (pin "2") (pinfunction "2_2") (pintype "passive"))
      (node (ref "R22") (pin "1") (pinfunction "1_1") (pintype "passive"))
      (node (ref "R2X") (pin "2") (pinfunction "2_2") (pintype "passive"))
      (node (ref "R3") (pin "2") (pinfunction "2_2") (pintype "passive"))
      (node (ref "R6") (pin "2") (pinfunction "2_2") (pintype "passive"))
      (node (ref "R9") (pin "2") (pinfunction "2_2") (pintype "passive"))
      (node (ref "SENSOR") (pin "A21") (pinfunction "GND_A21") (pintype "power_in"))
      (node (ref "SENSOR") (pin "A25") (pinfunction "GND_A25") (pintype "power_in"))
      (node (ref "SENSOR") (pin "A28") (pinfunction "GND_A28") (pintype "power_in"))
      (node (ref "SENSOR") (pin "A29") (pinfunction "GND_A29") (pintype "power_in"))
      (node (ref "SENSOR") (pin "A9") (pinfunction "GND_A9") (pintype "power_in"))
      (node (ref "SENSOR") (pin "B22") (pinfunction "GND_B22") (pintype "power_in"))
      (node (ref "SENSOR") (pin "B26") (pinfunction "GND_B26") (pintype "power_in"))
      (node (ref "SENSOR") (pin "B27") (pinfunction "GND_B27") (pintype "power_in"))
      (node (ref "SENSOR") (pin "B28") (pinfunction "GND_B28") (pintype "power_in"))
      (node (ref "SENSOR") (pin "B5") (pinfunction "GND_B5") (pintype "power_in"))
      (node (ref "SENSOR") (pin "C15") (pinfunction "GND_C15") (pintype "power_in"))
      (node (ref "SENSOR") (pin "C16") (pinfunction "GND_C16") (pintype "power_in"))
      (node (ref "SENSOR") (pin "C28") (pinfunction "GND_C28") (pintype "power_in"))
      (node (ref "SENSOR") (pin "D2") (pinfunction "GND_D2") (pintype "power_in"))
      (node (ref "SENSOR") (pin "D25") (pinfunction "GND_D25") (pintype "power_in"))
      (node (ref "SENSOR") (pin "D27") (pinfunction "GND_D27") (pintype "power_in"))
      (node (ref "SENSOR") (pin "D29") (pinfunction "GND_D29") (pintype "power_in"))
      (node (ref "SENSOR") (pin "E15") (pinfunction "GND_E15") (pintype "power_in"))
      (node (ref "SENSOR") (pin "E16") (pinfunction "GND_E16") (pintype "power_in"))
      (node (ref "SENSOR") (pin "E25") (pinfunction "GND_E25") (pintype "power_in"))
      (node (ref "SENSOR") (pin "E27") (pinfunction "GND_E27") (pintype "power_in"))
      (node (ref "SENSOR") (pin "E3") (pinfunction "GND_E3") (pintype "power_in"))
      (node (ref "SENSOR") (pin "F27") (pinfunction "GND_F27") (pintype "power_in"))
      (node (ref "SENSOR") (pin "G5") (pinfunction "GND_G5") (pintype "power_in"))
      (node (ref "SENSOR") (pin "H1") (pinfunction "GND_H1") (pintype "power_in"))
      (node (ref "SENSOR") (pin "H21") (pinfunction "GND_H21") (pintype "power_in"))
      (node (ref "SENSOR") (pin "H25") (pinfunction "GND_H25") (pintype "power_in"))
      (node (ref "SENSOR") (pin "H27") (pinfunction "GND_H27") (pintype "power_in"))
      (node (ref "SENSOR") (pin "H6") (pinfunction "GND_H6") (pintype "power_in"))
      (node (ref "SENSOR") (pin "H9") (pinfunction "GND_H9") (pintype "power_in"))
      (node (ref "U1") (pin "6") (pinfunction "ANODE_6") (pintype "input"))
      (node (ref "U2") (pin "6") (pinfunction "ANODE_6") (pintype "input"))
      (node (ref "U3") (pin "2") (pinfunction "GND_2") (pintype "power_in"))
      (node (ref "U3") (pin "EP") (pinfunction "EP_EP") (pintype "power_in"))
      (node (ref "U4") (pin "1") (pinfunction "~{1OE}_1") (pintype "input"))
      (node (ref "U4") (pin "10") (pinfunction "GND_10") (pintype "passive"))
      (node (ref "U4") (pin "11") (pinfunction "GND_11") (pintype "passive"))
      (node (ref "U4") (pin "16") (pinfunction "~{2OE}_16") (pintype "input"))
      (node (ref "U4") (pin "4") (pinfunction "1DIR_4") (pintype "input"))
      (node (ref "U4") (pin "9") (pinfunction "2A2_9") (pintype "output"))
      (node (ref "U5") (pin "6") (pinfunction "DIR4_6") (pintype "input"))
      (node (ref "U5") (pin "7") (pinfunction "~{OE}_7") (pintype "input"))
      (node (ref "U5") (pin "8") (pinfunction "GND_8") (pintype "passive"))
      (node (ref "U6") (pin "15") (pinfunction "DIR1_15") (pintype "input"))
      (node (ref "U6") (pin "5") (pinfunction "DIR3_5") (pintype "input"))
      (node (ref "U6") (pin "6") (pinfunction "DIR4_6") (pintype "input"))
      (node (ref "U6") (pin "7") (pinfunction "~{OE}_7") (pintype "input"))
      (node (ref "U6") (pin "8") (pinfunction "GND_8") (pintype "passive"))
      (node (ref "UEP") (pin "1") (pinfunction "A0_1") (pintype "input"))
      (node (ref "UEP") (pin "2") (pinfunction "A1_2") (pintype "input"))
      (node (ref "UEP") (pin "3") (pinfunction "A2_3") (pintype "input"))
      (node (ref "UEP") (pin "4") (pinfunction "GND_4") (pintype "passive"))
      (node (ref "UEP") (pin "EP") (pinfunction "EP_EP") (pintype "passive"))
      (node (ref "UNE") (pin "4") (pinfunction "VSS_4") (pintype "power_in"))
      (node (ref "UNE") (pin "EP") (pinfunction "EP_EP") (pintype "passive"))
      (node (ref "UNN") (pin "4") (pinfunction "VSS_4") (pintype "power_in"))
      (node (ref "UNN") (pin "EP") (pinfunction "EP_EP") (pintype "passive"))
      (node (ref "UNW") (pin "4") (pinfunction "VSS_4") (pintype "power_in"))
      (node (ref "UNW") (pin "EP") (pinfunction "EP_EP") (pintype "passive"))
      (node (ref "USE") (pin "4") (pinfunction "VSS_4") (pintype "power_in"))
      (node (ref "USE") (pin "EP") (pinfunction "EP_EP") (pintype "passive"))
      (node (ref "USS") (pin "4") (pinfunction "VSS_4") (pintype "power_in"))
      (node (ref "USS") (pin "EP") (pinfunction "EP_EP") (pintype "passive"))
      (node (ref "USW") (pin "4") (pinfunction "VSS_4") (pintype "power_in"))
      (node (ref "USW") (pin "EP") (pinfunction "EP_EP") (pintype "passive"))
      (node (ref "X-NORTH") (pin "102") (pinfunction "102_102") (pintype "bidirectional"))
      (node (ref "X-NORTH") (pin "103") (pinfunction "103_103") (pintype "bidirectional"))
      (node (ref "X-NORTH") (pin "108") (pinfunction "108_108") (pintype "bidirectional"))
      (node (ref "X-NORTH") (pin "114") (pinfunction "114_114") (pintype "bidirectional"))
      (node (ref "X-NORTH") (pin "12") (pinfunction "12_12") (pintype "bidirectional"))
      (node (ref "X-NORTH") (pin "120") (pinfunction "120_120") (pintype "bidirectional"))
      (node (ref "X-NORTH") (pin "126") (pinfunction "126_126") (pintype "bidirectional"))
      (node (ref "X-NORTH") (pin "132") (pinfunction "132_132") (pintype "bidirectional"))
      (node (ref "X-NORTH") (pin "138") (pinfunction "138_138") (pintype "bidirectional"))
      (node (ref "X-NORTH") (pin "139") (pinfunction "139_139") (pintype "bidirectional"))
      (node (ref "X-NORTH") (pin "18") (pinfunction "18_18") (pintype "bidirectional"))
      (node (ref "X-NORTH") (pin "24") (pinfunction "24_24") (pintype "bidirectional"))
      (node (ref "X-NORTH") (pin "30") (pinfunction "30_30") (pintype "bidirectional"))
      (node (ref "X-NORTH") (pin "36") (pinfunction "36_36") (pintype "bidirectional"))
      (node (ref "X-NORTH") (pin "42") (pinfunction "42_42") (pintype "bidirectional"))
      (node (ref "X-NORTH") (pin "43") (pinfunction "43_43") (pintype "bidirectional"))
      (node (ref "X-NORTH") (pin "48") (pinfunction "48_48") (pintype "bidirectional"))
      (node (ref "X-NORTH") (pin "54") (pinfunction "54_54") (pintype "bidirectional"))
      (node (ref "X-NORTH") (pin "60") (pinfunction "60_60") (pintype "bidirectional"))
      (node (ref "X-NORTH") (pin "66") (pinfunction "66_66") (pintype "bidirectional"))
      (node (ref "X-NORTH") (pin "72") (pinfunction "72_72") (pintype "bidirectional"))
      (node (ref "X-NORTH") (pin "78") (pinfunction "78_78") (pintype "bidirectional"))
      (node (ref "X-NORTH") (pin "84") (pinfunction "84_84") (pintype "bidirectional"))
      (node (ref "X-NORTH") (pin "90") (pinfunction "90_90") (pintype "bidirectional"))
      (node (ref "X-NORTH") (pin "96") (pinfunction "96_96") (pintype "bidirectional"))
      (node (ref "X-SOUTH") (pin "102") (pinfunction "102_102") (pintype "bidirectional"))
      (node (ref "X-SOUTH") (pin "103") (pinfunction "103_103") (pintype "bidirectional"))
      (node (ref "X-SOUTH") (pin "108") (pinfunction "108_108") (pintype "bidirectional"))
      (node (ref "X-SOUTH") (pin "114") (pinfunction "114_114") (pintype "bidirectional"))
      (node (ref "X-SOUTH") (pin "12") (pinfunction "12_12") (pintype "bidirectional"))
      (node (ref "X-SOUTH") (pin "120") (pinfunction "120_120") (pintype "bidirectional"))
      (node (ref "X-SOUTH") (pin "126") (pinfunction "126_126") (pintype "bidirectional"))
      (node (ref "X-SOUTH") (pin "132") (pinfunction "132_132") (pintype "bidirectional"))
      (node (ref "X-SOUTH") (pin "138") (pinfunction "138_138") (pintype "bidirectional"))
      (node (ref "X-SOUTH") (pin "139") (pinfunction "139_139") (pintype "bidirectional"))
      (node (ref "X-SOUTH") (pin "18") (pinfunction "18_18") (pintype "bidirectional"))
      (node (ref "X-SOUTH") (pin "24") (pinfunction "24_24") (pintype "bidirectional"))
      (node (ref "X-SOUTH") (pin "30") (pinfunction "30_30") (pintype "bidirectional"))
      (node (ref "X-SOUTH") (pin "36") (pinfunction "36_36") (pintype "bidirectional"))
      (node (ref "X-SOUTH") (pin "42") (pinfunction "42_42") (pintype "bidirectional"))
      (node (ref "X-SOUTH") (pin "43") (pinfunction "43_43") (pintype "bidirectional"))
      (node (ref "X-SOUTH") (pin "48") (pinfunction "48_48") (pintype "bidirectional"))
      (node (ref "X-SOUTH") (pin "54") (pinfunction "54_54") (pintype "bidirectional"))
      (node (ref "X-SOUTH") (pin "60") (pinfunction "60_60") (pintype "bidirectional"))
      (node (ref "X-SOUTH") (pin "66") (pinfunction "66_66") (pintype "bidirectional"))
      (node (ref "X-SOUTH") (pin "72") (pinfunction "72_72") (pintype "bidirectional"))
      (node (ref "X-SOUTH") (pin "78") (pinfunction "78_78") (pintype "bidirectional"))
      (node (ref "X-SOUTH") (pin "84") (pinfunction "84_84") (pintype "bidirectional"))
      (node (ref "X-SOUTH") (pin "90") (pinfunction "90_90") (pintype "bidirectional"))
      (node (ref "X-SOUTH") (pin "96") (pinfunction "96_96") (pintype "bidirectional"))
    )
    (net (code "4") (name "N$38") (class "Default")
      (node (ref "SENSOR") (pin "F4") (pinfunction "DIO1_F4") (pintype "output"))
    )
    (net (code "5") (name "N$39") (class "Default")
      (node (ref "SENSOR") (pin "E4") (pinfunction "DIO2_E4") (pintype "output"))
    )
    (net (code "6") (name "N$40") (class "Default")
      (node (ref "SENSOR") (pin "H4") (pinfunction "DIO3_H4") (pintype "output"))
    )
    (net (code "7") (name "N$41") (class "Default")
      (node (ref "SENSOR") (pin "G3") (pinfunction "DIO4_G3") (pintype "output"))
    )
    (net (code "8") (name "N$42") (class "Default")
      (node (ref "SENSOR") (pin "A2") (pinfunction "TANA_A2") (pintype "output"))
    )
    (net (code "9") (name "N00_N") (class "Default")
      (node (ref "R25") (pin "2") (pinfunction "2_2") (pintype "passive"))
      (node (ref "SENSOR") (pin "E6") (pinfunction "LVDS_CLK_P_E6") (pintype "input"))
      (node (ref "X-NORTH") (pin "16") (pinfunction "16_16") (pintype "bidirectional"))
    )
    (net (code "10") (name "N00_P") (class "Default")
      (node (ref "R25") (pin "1") (pinfunction "1_1") (pintype "passive"))
      (node (ref "SENSOR") (pin "E5") (pinfunction "LVDS_CLK_N_E5") (pintype "input"))
      (node (ref "X-NORTH") (pin "14") (pinfunction "14_14") (pintype "bidirectional"))
    )
    (net (code "11") (name "N01_N") (class "Default")
      (node (ref "SENSOR") (pin "G7") (pinfunction "OUTCLK_P_G7") (pintype "output"))
      (node (ref "X-NORTH") (pin "17") (pinfunction "17_17") (pintype "bidirectional"))
    )
    (net (code "12") (name "N01_P") (class "Default")
      (node (ref "SENSOR") (pin "G6") (pinfunction "OUTCLK_N_G6") (pintype "output"))
      (node (ref "X-NORTH") (pin "15") (pinfunction "15_15") (pintype "bidirectional"))
    )
    (net (code "13") (name "N02_N") (class "Default")
      (node (ref "SENSOR") (pin "F7") (pinfunction "OUT33_P_F7") (pintype "output"))
      (node (ref "X-NORTH") (pin "22") (pinfunction "22_22") (pintype "bidirectional"))
    )
    (net (code "14") (name "N02_P") (class "Default")
      (node (ref "SENSOR") (pin "F6") (pinfunction "OUT33_N_F6") (pintype "output"))
      (node (ref "X-NORTH") (pin "20") (pinfunction "20_20") (pintype "bidirectional"))
    )
    (net (code "15") (name "N03_N") (class "Default")
      (node (ref "X-NORTH") (pin "23") (pinfunction "23_23") (pintype "bidirectional"))
    )
    (net (code "16") (name "N03_P") (class "Default")
      (node (ref "X-NORTH") (pin "21") (pinfunction "21_21") (pintype "bidirectional"))
    )
    (net (code "17") (name "N04_N") (class "Default")
      (node (ref "SENSOR") (pin "E8") (pinfunction "OUT35_P_E8") (pintype "output"))
      (node (ref "X-NORTH") (pin "28") (pinfunction "28_28") (pintype "bidirectional"))
    )
    (net (code "18") (name "N04_P") (class "Default")
      (node (ref "SENSOR") (pin "E7") (pinfunction "OUT35_N_E7") (pintype "output"))
      (node (ref "X-NORTH") (pin "26") (pinfunction "26_26") (pintype "bidirectional"))
    )
    (net (code "19") (name "N05_N") (class "Default")
      (node (ref "SENSOR") (pin "H8") (pinfunction "OUT34_P_H8") (pintype "output"))
      (node (ref "X-NORTH") (pin "29") (pinfunction "29_29") (pintype "bidirectional"))
    )
    (net (code "20") (name "N05_P") (class "Default")
      (node (ref "SENSOR") (pin "H7") (pinfunction "OUT34_N_H7") (pintype "output"))
      (node (ref "X-NORTH") (pin "27") (pinfunction "27_27") (pintype "bidirectional"))
    )
    (net (code "21") (name "N06_N") (class "Default")
      (node (ref "SENSOR") (pin "F9") (pinfunction "OUT37_P_F9") (pintype "output"))
      (node (ref "X-NORTH") (pin "34") (pinfunction "34_34") (pintype "bidirectional"))
    )
    (net (code "22") (name "N06_P") (class "Default")
      (node (ref "SENSOR") (pin "F8") (pinfunction "OUT37_N_F8") (pintype "output"))
      (node (ref "X-NORTH") (pin "32") (pinfunction "32_32") (pintype "bidirectional"))
    )
    (net (code "23") (name "N07_N") (class "Default")
      (node (ref "SENSOR") (pin "G9") (pinfunction "OUT36_P_G9") (pintype "output"))
      (node (ref "X-NORTH") (pin "35") (pinfunction "35_35") (pintype "bidirectional"))
    )
    (net (code "24") (name "N07_P") (class "Default")
      (node (ref "SENSOR") (pin "G8") (pinfunction "OUT36_N_G8") (pintype "output"))
      (node (ref "X-NORTH") (pin "33") (pinfunction "33_33") (pintype "bidirectional"))
    )
    (net (code "25") (name "N08_N") (class "Default")
      (node (ref "SENSOR") (pin "E10") (pinfunction "OUT38_P_E10") (pintype "output"))
      (node (ref "X-NORTH") (pin "40") (pinfunction "40_40") (pintype "bidirectional"))
    )
    (net (code "26") (name "N08_P") (class "Default")
      (node (ref "SENSOR") (pin "E9") (pinfunction "OUT38_N_E9") (pintype "output"))
      (node (ref "X-NORTH") (pin "38") (pinfunction "38_38") (pintype "bidirectional"))
    )
    (net (code "27") (name "N09_N") (class "Default")
      (node (ref "SENSOR") (pin "G11") (pinfunction "OUT39_P_G11") (pintype "output"))
      (node (ref "X-NORTH") (pin "41") (pinfunction "41_41") (pintype "bidirectional"))
    )
    (net (code "28") (name "N09_P") (class "Default")
      (node (ref "SENSOR") (pin "G10") (pinfunction "OUT39_N_G10") (pintype "output"))
      (node (ref "X-NORTH") (pin "39") (pinfunction "39_39") (pintype "bidirectional"))
    )
    (net (code "29") (name "N10_N") (class "Default")
      (node (ref "SENSOR") (pin "F11") (pinfunction "OUT40_P_F11") (pintype "output"))
      (node (ref "X-NORTH") (pin "46") (pinfunction "46_46") (pintype "bidirectional"))
    )
    (net (code "30") (name "N10_P") (class "Default")
      (node (ref "SENSOR") (pin "F10") (pinfunction "OUT40_N_F10") (pintype "output"))
      (node (ref "X-NORTH") (pin "44") (pinfunction "44_44") (pintype "bidirectional"))
    )
    (net (code "31") (name "N11_N") (class "Default")
      (node (ref "SENSOR") (pin "H12") (pinfunction "OUT41_P_H12") (pintype "output"))
      (node (ref "X-NORTH") (pin "47") (pinfunction "47_47") (pintype "bidirectional"))
    )
    (net (code "32") (name "N11_P") (class "Default")
      (node (ref "SENSOR") (pin "H11") (pinfunction "OUT41_N_H11") (pintype "output"))
      (node (ref "X-NORTH") (pin "45") (pinfunction "45_45") (pintype "bidirectional"))
    )
    (net (code "33") (name "N12_N") (class "Default")
      (node (ref "SENSOR") (pin "E12") (pinfunction "OUT42_P_E12") (pintype "output"))
      (node (ref "X-NORTH") (pin "52") (pinfunction "52_52") (pintype "bidirectional"))
    )
    (net (code "34") (name "N12_P") (class "Default")
      (node (ref "SENSOR") (pin "E11") (pinfunction "OUT42_N_E11") (pintype "output"))
      (node (ref "X-NORTH") (pin "50") (pinfunction "50_50") (pintype "bidirectional"))
    )
    (net (code "35") (name "N13_N") (class "Default")
      (node (ref "SENSOR") (pin "G13") (pinfunction "OUT43_P_G13") (pintype "output"))
      (node (ref "X-NORTH") (pin "53") (pinfunction "53_53") (pintype "bidirectional"))
    )
    (net (code "36") (name "N13_P") (class "Default")
      (node (ref "SENSOR") (pin "G12") (pinfunction "OUT43_N_G12") (pintype "output"))
      (node (ref "X-NORTH") (pin "51") (pinfunction "51_51") (pintype "bidirectional"))
    )
    (net (code "37") (name "N14_N") (class "Default")
      (node (ref "SENSOR") (pin "F13") (pinfunction "OUT44_P_F13") (pintype "output"))
      (node (ref "X-NORTH") (pin "58") (pinfunction "58_58") (pintype "bidirectional"))
    )
    (net (code "38") (name "N14_P") (class "Default")
      (node (ref "SENSOR") (pin "F12") (pinfunction "OUT44_N_F12") (pintype "output"))
      (node (ref "X-NORTH") (pin "56") (pinfunction "56_56") (pintype "bidirectional"))
    )
    (net (code "39") (name "N15_N") (class "Default")
      (node (ref "SENSOR") (pin "H14") (pinfunction "OUT45_P_H14") (pintype "output"))
      (node (ref "X-NORTH") (pin "59") (pinfunction "59_59") (pintype "bidirectional"))
    )
    (net (code "40") (name "N15_P") (class "Default")
      (node (ref "SENSOR") (pin "H13") (pinfunction "OUT45_N_H13") (pintype "output"))
      (node (ref "X-NORTH") (pin "57") (pinfunction "57_57") (pintype "bidirectional"))
    )
    (net (code "41") (name "N16_N") (class "Default")
      (node (ref "SENSOR") (pin "E14") (pinfunction "OUT46_P_E14") (pintype "output"))
      (node (ref "X-NORTH") (pin "64") (pinfunction "64_64") (pintype "bidirectional"))
    )
    (net (code "42") (name "N16_P") (class "Default")
      (node (ref "SENSOR") (pin "E13") (pinfunction "OUT46_N_E13") (pintype "output"))
      (node (ref "X-NORTH") (pin "62") (pinfunction "62_62") (pintype "bidirectional"))
    )
    (net (code "43") (name "N17_N") (class "Default")
      (node (ref "SENSOR") (pin "G15") (pinfunction "OUT47_P_G15") (pintype "output"))
      (node (ref "X-NORTH") (pin "65") (pinfunction "65_65") (pintype "bidirectional"))
    )
    (net (code "44") (name "N17_P") (class "Default")
      (node (ref "SENSOR") (pin "G14") (pinfunction "OUT47_N_G14") (pintype "output"))
      (node (ref "X-NORTH") (pin "63") (pinfunction "63_63") (pintype "bidirectional"))
    )
    (net (code "45") (name "N18_N") (class "Default")
      (node (ref "SENSOR") (pin "F15") (pinfunction "OUT48_P_F15") (pintype "output"))
      (node (ref "X-NORTH") (pin "70") (pinfunction "70_70") (pintype "bidirectional"))
    )
    (net (code "46") (name "N18_P") (class "Default")
      (node (ref "SENSOR") (pin "F14") (pinfunction "OUT48_N_F14") (pintype "output"))
      (node (ref "X-NORTH") (pin "68") (pinfunction "68_68") (pintype "bidirectional"))
    )
    (net (code "47") (name "N19_N") (class "Default")
      (node (ref "SENSOR") (pin "G17") (pinfunction "OUT50_P_G17") (pintype "output"))
      (node (ref "X-NORTH") (pin "71") (pinfunction "71_71") (pintype "bidirectional"))
    )
    (net (code "48") (name "N19_P") (class "Default")
      (node (ref "SENSOR") (pin "G16") (pinfunction "OUT50_N_G16") (pintype "output"))
      (node (ref "X-NORTH") (pin "69") (pinfunction "69_69") (pintype "bidirectional"))
    )
    (net (code "49") (name "N20_N") (class "Default")
      (node (ref "SENSOR") (pin "F17") (pinfunction "OUT49_P_F17") (pintype "output"))
      (node (ref "X-NORTH") (pin "76") (pinfunction "76_76") (pintype "bidirectional"))
    )
    (net (code "50") (name "N20_P") (class "Default")
      (node (ref "SENSOR") (pin "F16") (pinfunction "OUT49_N_F16") (pintype "output"))
      (node (ref "X-NORTH") (pin "74") (pinfunction "74_74") (pintype "bidirectional"))
    )
    (net (code "51") (name "N21_N") (class "Default")
      (node (ref "SENSOR") (pin "H18") (pinfunction "OUT52_P_H18") (pintype "output"))
      (node (ref "X-NORTH") (pin "77") (pinfunction "77_77") (pintype "bidirectional"))
    )
    (net (code "52") (name "N21_P") (class "Default")
      (node (ref "SENSOR") (pin "H17") (pinfunction "OUT52_N_H17") (pintype "output"))
      (node (ref "X-NORTH") (pin "75") (pinfunction "75_75") (pintype "bidirectional"))
    )
    (net (code "53") (name "N22_N") (class "Default")
      (node (ref "SENSOR") (pin "E18") (pinfunction "OUT51_P_E18") (pintype "output"))
      (node (ref "X-NORTH") (pin "82") (pinfunction "82_82") (pintype "bidirectional"))
    )
    (net (code "54") (name "N22_P") (class "Default")
      (node (ref "SENSOR") (pin "E17") (pinfunction "OUT51_N_E17") (pintype "output"))
      (node (ref "X-NORTH") (pin "80") (pinfunction "80_80") (pintype "bidirectional"))
    )
    (net (code "55") (name "N23_N") (class "Default")
      (node (ref "SENSOR") (pin "G19") (pinfunction "OUT54_P_G19") (pintype "output"))
      (node (ref "X-NORTH") (pin "83") (pinfunction "83_83") (pintype "bidirectional"))
    )
    (net (code "56") (name "N23_P") (class "Default")
      (node (ref "SENSOR") (pin "G18") (pinfunction "OUT54_N_G18") (pintype "output"))
      (node (ref "X-NORTH") (pin "81") (pinfunction "81_81") (pintype "bidirectional"))
    )
    (net (code "57") (name "N24_N") (class "Default")
      (node (ref "SENSOR") (pin "F19") (pinfunction "OUT53_P_F19") (pintype "output"))
      (node (ref "X-NORTH") (pin "88") (pinfunction "88_88") (pintype "bidirectional"))
    )
    (net (code "58") (name "N24_P") (class "Default")
      (node (ref "SENSOR") (pin "F18") (pinfunction "OUT53_N_F18") (pintype "output"))
      (node (ref "X-NORTH") (pin "86") (pinfunction "86_86") (pintype "bidirectional"))
    )
    (net (code "59") (name "N25_N") (class "Default")
      (node (ref "SENSOR") (pin "H20") (pinfunction "OUT56_P_H20") (pintype "output"))
      (node (ref "X-NORTH") (pin "89") (pinfunction "89_89") (pintype "bidirectional"))
    )
    (net (code "60") (name "N25_P") (class "Default")
      (node (ref "SENSOR") (pin "H19") (pinfunction "OUT56_N_H19") (pintype "output"))
      (node (ref "X-NORTH") (pin "87") (pinfunction "87_87") (pintype "bidirectional"))
    )
    (net (code "61") (name "N26_N") (class "Default")
      (node (ref "SENSOR") (pin "E20") (pinfunction "OUT55_P_E20") (pintype "output"))
      (node (ref "X-NORTH") (pin "94") (pinfunction "94_94") (pintype "bidirectional"))
    )
    (net (code "62") (name "N26_P") (class "Default")
      (node (ref "SENSOR") (pin "E19") (pinfunction "OUT55_N_E19") (pintype "output"))
      (node (ref "X-NORTH") (pin "92") (pinfunction "92_92") (pintype "bidirectional"))
    )
    (net (code "63") (name "N27_N") (class "Default")
      (node (ref "SENSOR") (pin "G21") (pinfunction "OUT58_P_G21") (pintype "output"))
      (node (ref "X-NORTH") (pin "95") (pinfunction "95_95") (pintype "bidirectional"))
    )
    (net (code "64") (name "N27_P") (class "Default")
      (node (ref "SENSOR") (pin "G20") (pinfunction "OUT58_N_G20") (pintype "output"))
      (node (ref "X-NORTH") (pin "93") (pinfunction "93_93") (pintype "bidirectional"))
    )
    (net (code "65") (name "N28_N") (class "Default")
      (node (ref "SENSOR") (pin "F21") (pinfunction "OUT57_P_F21") (pintype "output"))
      (node (ref "X-NORTH") (pin "100") (pinfunction "100_100") (pintype "bidirectional"))
    )
    (net (code "66") (name "N28_P") (class "Default")
      (node (ref "SENSOR") (pin "F20") (pinfunction "OUT57_N_F20") (pintype "output"))
      (node (ref "X-NORTH") (pin "98") (pinfunction "98_98") (pintype "bidirectional"))
    )
    (net (code "67") (name "N29_N") (class "Default")
      (node (ref "SENSOR") (pin "G23") (pinfunction "OUT61_P_G23") (pintype "output"))
      (node (ref "X-NORTH") (pin "101") (pinfunction "101_101") (pintype "bidirectional"))
    )
    (net (code "68") (name "N29_P") (class "Default")
      (node (ref "SENSOR") (pin "G22") (pinfunction "OUT61_N_G22") (pintype "output"))
      (node (ref "X-NORTH") (pin "99") (pinfunction "99_99") (pintype "bidirectional"))
    )
    (net (code "69") (name "N30_N") (class "Default")
      (node (ref "SENSOR") (pin "E22") (pinfunction "OUT59_P_E22") (pintype "output"))
      (node (ref "X-NORTH") (pin "106") (pinfunction "106_106") (pintype "bidirectional"))
    )
    (net (code "70") (name "N30_P") (class "Default")
      (node (ref "SENSOR") (pin "E21") (pinfunction "OUT59_N_E21") (pintype "output"))
      (node (ref "X-NORTH") (pin "104") (pinfunction "104_104") (pintype "bidirectional"))
    )
    (net (code "71") (name "N31_N") (class "Default")
      (node (ref "SENSOR") (pin "H24") (pinfunction "OUT63_P_H24") (pintype "output"))
      (node (ref "X-NORTH") (pin "107") (pinfunction "107_107") (pintype "bidirectional"))
    )
    (net (code "72") (name "N31_P") (class "Default")
      (node (ref "SENSOR") (pin "H23") (pinfunction "OUT63_N_H23") (pintype "output"))
      (node (ref "X-NORTH") (pin "105") (pinfunction "105_105") (pintype "bidirectional"))
    )
    (net (code "73") (name "N32_N") (class "Default")
      (node (ref "SENSOR") (pin "F23") (pinfunction "OUT60_P_F23") (pintype "output"))
      (node (ref "X-NORTH") (pin "112") (pinfunction "112_112") (pintype "bidirectional"))
    )
    (net (code "74") (name "N32_P") (class "Default")
      (node (ref "SENSOR") (pin "F22") (pinfunction "OUT60_N_F22") (pintype "output"))
      (node (ref "X-NORTH") (pin "110") (pinfunction "110_110") (pintype "bidirectional"))
    )
    (net (code "75") (name "N33_N") (class "Default")
      (node (ref "SENSOR") (pin "G25") (pinfunction "OUT64_P_G25") (pintype "output"))
      (node (ref "X-NORTH") (pin "113") (pinfunction "113_113") (pintype "bidirectional"))
    )
    (net (code "76") (name "N33_P") (class "Default")
      (node (ref "SENSOR") (pin "G24") (pinfunction "OUT64_N_G24") (pintype "output"))
      (node (ref "X-NORTH") (pin "111") (pinfunction "111_111") (pintype "bidirectional"))
    )
    (net (code "77") (name "N34_N") (class "Default")
      (node (ref "SENSOR") (pin "E24") (pinfunction "OUT62_P_E24") (pintype "output"))
      (node (ref "X-NORTH") (pin "118") (pinfunction "118_118") (pintype "bidirectional"))
    )
    (net (code "78") (name "N34_P") (class "Default")
      (node (ref "SENSOR") (pin "E23") (pinfunction "OUT62_N_E23") (pintype "output"))
      (node (ref "X-NORTH") (pin "116") (pinfunction "116_116") (pintype "bidirectional"))
    )
    (net (code "79") (name "N35_N") (class "Default")
      (node (ref "U6") (pin "4") (pinfunction "A4_4") (pintype "bidirectional"))
      (node (ref "X-NORTH") (pin "119") (pinfunction "119_119") (pintype "bidirectional"))
    )
    (net (code "80") (name "N35_P") (class "Default")
      (node (ref "U6") (pin "3") (pinfunction "A3_3") (pintype "bidirectional"))
      (node (ref "X-NORTH") (pin "117") (pinfunction "117_117") (pintype "bidirectional"))
    )
    (net (code "81") (name "N36_N") (class "Default")
      (node (ref "X-NORTH") (pin "124") (pinfunction "124_124") (pintype "bidirectional"))
    )
    (net (code "82") (name "N36_P") (class "Default")
      (node (ref "X-NORTH") (pin "122") (pinfunction "122_122") (pintype "bidirectional"))
    )
    (net (code "83") (name "N37_N") (class "Default")
      (node (ref "U5") (pin "3") (pinfunction "A3_3") (pintype "bidirectional"))
      (node (ref "X-NORTH") (pin "125") (pinfunction "125_125") (pintype "bidirectional"))
    )
    (net (code "84") (name "N37_P") (class "Default")
      (node (ref "U5") (pin "4") (pinfunction "A4_4") (pintype "bidirectional"))
      (node (ref "X-NORTH") (pin "123") (pinfunction "123_123") (pintype "bidirectional"))
    )
    (net (code "85") (name "N38_N") (class "Default")
      (node (ref "U6") (pin "2") (pinfunction "A2_2") (pintype "bidirectional"))
      (node (ref "X-NORTH") (pin "130") (pinfunction "130_130") (pintype "bidirectional"))
    )
    (net (code "86") (name "N38_P") (class "Default")
      (node (ref "U6") (pin "1") (pinfunction "A1_1") (pintype "bidirectional"))
      (node (ref "X-NORTH") (pin "128") (pinfunction "128_128") (pintype "bidirectional"))
    )
    (net (code "87") (name "N39_N") (class "Default")
      (node (ref "U5") (pin "1") (pinfunction "A1_1") (pintype "bidirectional"))
      (node (ref "X-NORTH") (pin "131") (pinfunction "131_131") (pintype "bidirectional"))
    )
    (net (code "88") (name "N39_P") (class "Default")
      (node (ref "U5") (pin "2") (pinfunction "A2_2") (pintype "bidirectional"))
      (node (ref "X-NORTH") (pin "129") (pinfunction "129_129") (pintype "bidirectional"))
    )
    (net (code "89") (name "N_CHK_V") (class "Default")
      (node (ref "C2") (pin "1") (pinfunction "1_1") (pintype "passive"))
      (node (ref "C3") (pin "1") (pinfunction "1_1") (pintype "passive"))
      (node (ref "C4") (pin "1") (pinfunction "1_1") (pintype "passive"))
      (node (ref "R19") (pin "1") (pinfunction "1_1") (pintype "passive"))
      (node (ref "TP1") (pin "TP") (pinfunction "TP_TP") (pintype "input"))
      (node (ref "UNE") (pin "8") (pinfunction "VDD_8") (pintype "power_in"))
      (node (ref "UNN") (pin "8") (pinfunction "VDD_8") (pintype "power_in"))
      (node (ref "UNW") (pin "8") (pinfunction "VDD_8") (pintype "power_in"))
      (node (ref "X-NORTH") (pin "10") (pinfunction "10_10") (pintype "bidirectional"))
      (node (ref "X-NORTH") (pin "8") (pinfunction "8_8") (pintype "bidirectional"))
    )
    (net (code "90") (name "N_I2C_V") (class "Default")
      (node (ref "C1") (pin "1") (pinfunction "1_1") (pintype "passive"))
      (node (ref "R1X") (pin "1") (pinfunction "1_1") (pintype "passive"))
      (node (ref "UEP") (pin "8") (pinfunction "VCC_8") (pintype "power_in"))
      (node (ref "X-NORTH") (pin "135") (pinfunction "135_135") (pintype "bidirectional"))
      (node (ref "X-NORTH") (pin "137") (pinfunction "137_137") (pintype "bidirectional"))
    )
    (net (code "91") (name "N_REF") (class "Default")
      (node (ref "R19") (pin "2") (pinfunction "2_2") (pintype "passive"))
      (node (ref "TP2") (pin "TP") (pinfunction "TP_TP") (pintype "input"))
      (node (ref "U1") (pin "1") (pinfunction "CATHODE_1") (pintype "output"))
      (node (ref "U1") (pin "3") (pinfunction "REF_3") (pintype "input"))
      (node (ref "UNE") (pin "2") (pinfunction "VINA-_2") (pintype "input"))
      (node (ref "UNE") (pin "5") (pinfunction "VINB+_5") (pintype "input"))
      (node (ref "UNN") (pin "2") (pinfunction "VINA-_2") (pintype "input"))
      (node (ref "UNN") (pin "5") (pinfunction "VINB+_5") (pintype "input"))
      (node (ref "UNW") (pin "2") (pinfunction "VINA-_2") (pintype "input"))
      (node (ref "UNW") (pin "5") (pinfunction "VINB+_5") (pintype "input"))
    )
    (net (code "92") (name "N_SCK") (class "Default")
      (node (ref "U4") (pin "15") (pinfunction "1B1_15") (pintype "output"))
      (node (ref "X-NORTH") (pin "144") (pinfunction "144_144") (pintype "bidirectional"))
    )
    (net (code "93") (name "N_SCL") (class "Default")
      (node (ref "UEP") (pin "6") (pinfunction "SCL_6") (pintype "input"))
      (node (ref "X-NORTH") (pin "143") (pinfunction "143_143") (pintype "bidirectional"))
    )
    (net (code "94") (name "N_SDA") (class "Default")
      (node (ref "UEP") (pin "5") (pinfunction "SDA_5") (pintype "bidirectional"))
      (node (ref "X-NORTH") (pin "141") (pinfunction "141_141") (pintype "bidirectional"))
    )
    (net (code "95") (name "N_SDI") (class "Default")
      (node (ref "U4") (pin "13") (pinfunction "2B1_13") (pintype "output"))
      (node (ref "X-NORTH") (pin "140") (pinfunction "140_140") (pintype "bidirectional"))
    )
    (net (code "96") (name "N_SDO") (class "Default")
      (node (ref "U4") (pin "14") (pinfunction "1B2_14") (pintype "output"))
      (node (ref "X-NORTH") (pin "142") (pinfunction "142_142") (pintype "bidirectional"))
    )
    (net (code "97") (name "N_SPI_V") (class "Default")
      (node (ref "C59") (pin "1") (pinfunction "1_1") (pintype "passive"))
      (node (ref "U4") (pin "2") (pinfunction "VCCB_2") (pintype "power_in"))
      (node (ref "X-NORTH") (pin "134") (pinfunction "134_134") (pintype "bidirectional"))
      (node (ref "X-NORTH") (pin "136") (pinfunction "136_136") (pintype "bidirectional"))
    )
    (net (code "98") (name "N_VE") (class "Default")
      (node (ref "C50") (pin "1") (pinfunction "1_1") (pintype "passive"))
      (node (ref "C51") (pin "1") (pinfunction "1_1") (pintype "passive"))
      (node (ref "C52") (pin "1") (pinfunction "1_1") (pintype "passive"))
      (node (ref "C53") (pin "1") (pinfunction "1_1") (pintype "passive"))
      (node (ref "C54") (pin "1") (pinfunction "1_1") (pintype "passive"))
      (node (ref "C55") (pin "1") (pinfunction "1_1") (pintype "passive"))
      (node (ref "C56") (pin "1") (pinfunction "1_1") (pintype "passive"))
      (node (ref "C67") (pin "1") (pinfunction "1_1") (pintype "passive"))
      (node (ref "C69") (pin "1") (pinfunction "1_1") (pintype "passive"))
      (node (ref "C75") (pin "1") (pinfunction "1_1") (pintype "passive"))
      (node (ref "C76") (pin "1") (pinfunction "1_1") (pintype "passive"))
      (node (ref "C77") (pin "1") (pinfunction "1_1") (pintype "passive"))
      (node (ref "C84") (pin "1") (pinfunction "1_1") (pintype "passive"))
      (node (ref "C85") (pin "1") (pinfunction "1_1") (pintype "passive"))
      (node (ref "C86") (pin "1") (pinfunction "1_1") (pintype "passive"))
      (node (ref "SENSOR") (pin "C26") (pinfunction "VDD33_C26") (pintype "power_in"))
      (node (ref "SENSOR") (pin "C27") (pinfunction "VDD33_C27") (pintype "power_in"))
      (node (ref "SENSOR") (pin "D26") (pinfunction "VDD33_D26") (pintype "power_in"))
      (node (ref "SENSOR") (pin "D3") (pinfunction "VDD33_D3") (pintype "power_in"))
      (node (ref "SENSOR") (pin "E26") (pinfunction "VDD33_E26") (pintype "power_in"))
      (node (ref "SENSOR") (pin "F26") (pinfunction "VDD33_F26") (pintype "power_in"))
      (node (ref "SENSOR") (pin "F5") (pinfunction "VDD33_F5") (pintype "power_in"))
      (node (ref "TP7") (pin "TP") (pinfunction "TP_TP") (pintype "input"))
      (node (ref "U4") (pin "3") (pinfunction "VCCA_3") (pintype "power_in"))
      (node (ref "U4") (pin "5") (pinfunction "2DIR_5") (pintype "input"))
      (node (ref "U5") (pin "13") (pinfunction "VCCB_13") (pintype "power_in"))
      (node (ref "U6") (pin "13") (pinfunction "VCCB_13") (pintype "power_in"))
      (node (ref "X-NORTH") (pin "109") (pinfunction "109_109") (pintype "bidirectional"))
      (node (ref "X-NORTH") (pin "115") (pinfunction "115_115") (pintype "bidirectional"))
      (node (ref "X-NORTH") (pin "121") (pinfunction "121_121") (pintype "bidirectional"))
      (node (ref "X-NORTH") (pin "127") (pinfunction "127_127") (pintype "bidirectional"))
      (node (ref "X-NORTH") (pin "133") (pinfunction "133_133") (pintype "bidirectional"))
    )
    (net (code "99") (name "N_VE_CV") (class "Default")
      (node (ref "C10") (pin "1") (pinfunction "1_1") (pintype "passive"))
      (node (ref "R7") (pin "1") (pinfunction "1_1") (pintype "passive"))
      (node (ref "X-NORTH") (pin "6") (pinfunction "6_6") (pintype "bidirectional"))
    )
    (net (code "100") (name "N_VE_OV") (class "Default")
      (node (ref "UNE") (pin "7") (pinfunction "OUTB_7") (pintype "output"))
      (node (ref "X-NORTH") (pin "5") (pinfunction "5_5") (pintype "bidirectional"))
    )
    (net (code "101") (name "N_VE_UV") (class "Default")
      (node (ref "UNE") (pin "1") (pinfunction "OUTA_1") (pintype "output"))
      (node (ref "X-NORTH") (pin "11") (pinfunction "11_11") (pintype "bidirectional"))
    )
    (net (code "102") (name "N_VN") (class "Default")
      (node (ref "C31") (pin "1") (pinfunction "1_1") (pintype "passive"))
      (node (ref "C32") (pin "1") (pinfunction "1_1") (pintype "passive"))
      (node (ref "C33") (pin "1") (pinfunction "1_1") (pintype "passive"))
      (node (ref "C34") (pin "1") (pinfunction "1_1") (pintype "passive"))
      (node (ref "C35") (pin "1") (pinfunction "1_1") (pintype "passive"))
      (node (ref "C36") (pin "1") (pinfunction "1_1") (pintype "passive"))
      (node (ref "C37") (pin "1") (pinfunction "1_1") (pintype "passive"))
      (node (ref "C38") (pin "1") (pinfunction "1_1") (pintype "passive"))
      (node (ref "C39") (pin "1") (pinfunction "1_1") (pintype "passive"))
      (node (ref "C40") (pin "1") (pinfunction "1_1") (pintype "passive"))
      (node (ref "C41") (pin "1") (pinfunction "1_1") (pintype "passive"))
      (node (ref "C42") (pin "1") (pinfunction "1_1") (pintype "passive"))
      (node (ref "C43") (pin "1") (pinfunction "1_1") (pintype "passive"))
      (node (ref "C44") (pin "1") (pinfunction "1_1") (pintype "passive"))
      (node (ref "C68") (pin "1") (pinfunction "1_1") (pintype "passive"))
      (node (ref "C70") (pin "1") (pinfunction "1_1") (pintype "passive"))
      (node (ref "C78") (pin "1") (pinfunction "1_1") (pintype "passive"))
      (node (ref "C79") (pin "1") (pinfunction "1_1") (pintype "passive"))
      (node (ref "C80") (pin "1") (pinfunction "1_1") (pintype "passive"))
      (node (ref "C87") (pin "1") (pinfunction "1_1") (pintype "passive"))
      (node (ref "C88") (pin "1") (pinfunction "1_1") (pintype "passive"))
      (node (ref "C89") (pin "1") (pinfunction "1_1") (pintype "passive"))
      (node (ref "SENSOR") (pin "A10") (pinfunction "VDD18_A10") (pintype "power_in"))
      (node (ref "SENSOR") (pin "A15") (pinfunction "VDD18_A15") (pintype "power_in"))
      (node (ref "SENSOR") (pin "A16") (pinfunction "VDD18_A16") (pintype "power_in"))
      (node (ref "SENSOR") (pin "A22") (pinfunction "VDD18_A22") (pintype "power_in"))
      (node (ref "SENSOR") (pin "A26") (pinfunction "VDD18_A26") (pintype "power_in"))
      (node (ref "SENSOR") (pin "A27") (pinfunction "VDD18_A27") (pintype "power_in"))
      (node (ref "SENSOR") (pin "B4") (pinfunction "VDD18_B4") (pintype "power_in"))
      (node (ref "SENSOR") (pin "E1") (pinfunction "VDD18_PLL_E1") (pintype "power_in"))
      (node (ref "SENSOR") (pin "H10") (pinfunction "VDD18_H10") (pintype "power_in"))
      (node (ref "SENSOR") (pin "H15") (pinfunction "VDD18_H15") (pintype "power_in"))
      (node (ref "SENSOR") (pin "H16") (pinfunction "VDD18_H16") (pintype "power_in"))
      (node (ref "SENSOR") (pin "H22") (pinfunction "VDD18_H22") (pintype "power_in"))
      (node (ref "SENSOR") (pin "H26") (pinfunction "VDD18_H26") (pintype "power_in"))
      (node (ref "SENSOR") (pin "H5") (pinfunction "VDD18_H5") (pintype "power_in"))
      (node (ref "TP5") (pin "TP") (pinfunction "TP_TP") (pintype "input"))
      (node (ref "U5") (pin "14") (pinfunction "VCCA_14") (pintype "power_in"))
      (node (ref "U5") (pin "15") (pinfunction "DIR1_15") (pintype "input"))
      (node (ref "U5") (pin "16") (pinfunction "DIR2_16") (pintype "input"))
      (node (ref "U5") (pin "5") (pinfunction "DIR3_5") (pintype "input"))
      (node (ref "U6") (pin "14") (pinfunction "VCCA_14") (pintype "power_in"))
      (node (ref "U6") (pin "16") (pinfunction "DIR2_16") (pintype "input"))
      (node (ref "X-NORTH") (pin "49") (pinfunction "49_49") (pintype "bidirectional"))
      (node (ref "X-NORTH") (pin "55") (pinfunction "55_55") (pintype "bidirectional"))
      (node (ref "X-NORTH") (pin "61") (pinfunction "61_61") (pintype "bidirectional"))
      (node (ref "X-NORTH") (pin "67") (pinfunction "67_67") (pintype "bidirectional"))
      (node (ref "X-NORTH") (pin "73") (pinfunction "73_73") (pintype "bidirectional"))
      (node (ref "X-NORTH") (pin "79") (pinfunction "79_79") (pintype "bidirectional"))
      (node (ref "X-NORTH") (pin "85") (pinfunction "85_85") (pintype "bidirectional"))
      (node (ref "X-NORTH") (pin "91") (pinfunction "91_91") (pintype "bidirectional"))
      (node (ref "X-NORTH") (pin "97") (pinfunction "97_97") (pintype "bidirectional"))
    )
    (net (code "103") (name "N_VN_CV") (class "Default")
      (node (ref "C9") (pin "1") (pinfunction "1_1") (pintype "passive"))
      (node (ref "R4") (pin "1") (pinfunction "1_1") (pintype "passive"))
      (node (ref "X-NORTH") (pin "4") (pinfunction "4_4") (pintype "bidirectional"))
    )
    (net (code "104") (name "N_VN_OV") (class "Default")
      (node (ref "UNN") (pin "7") (pinfunction "OUTB_7") (pintype "output"))
      (node (ref "X-NORTH") (pin "3") (pinfunction "3_3") (pintype "bidirectional"))
    )
    (net (code "105") (name "N_VN_UV") (class "Default")
      (node (ref "UNN") (pin "1") (pinfunction "OUTA_1") (pintype "output"))
      (node (ref "X-NORTH") (pin "9") (pinfunction "9_9") (pintype "bidirectional"))
    )
    (net (code "106") (name "N_VW") (class "Default")
      (node (ref "C57") (pin "1") (pinfunction "1_1") (pintype "passive"))
      (node (ref "C58") (pin "1") (pinfunction "1_1") (pintype "passive"))
      (node (ref "C92") (pin "1") (pinfunction "1_1") (pintype "passive"))
      (node (ref "SENSOR") (pin "E2") (pinfunction "VDD_RES_E2") (pintype "power_in"))
      (node (ref "SENSOR") (pin "G4") (pinfunction "VDD_RES_G4") (pintype "power_in"))
      (node (ref "TP8") (pin "TP") (pinfunction "TP_TP") (pintype "input"))
      (node (ref "X-NORTH") (pin "13") (pinfunction "13_13") (pintype "bidirectional"))
      (node (ref "X-NORTH") (pin "19") (pinfunction "19_19") (pintype "bidirectional"))
      (node (ref "X-NORTH") (pin "25") (pinfunction "25_25") (pintype "bidirectional"))
      (node (ref "X-NORTH") (pin "31") (pinfunction "31_31") (pintype "bidirectional"))
      (node (ref "X-NORTH") (pin "37") (pinfunction "37_37") (pintype "bidirectional"))
    )
    (net (code "107") (name "N_VW_CV") (class "Default")
      (node (ref "C8") (pin "1") (pinfunction "1_1") (pintype "passive"))
      (node (ref "R1") (pin "1") (pinfunction "1_1") (pintype "passive"))
      (node (ref "X-NORTH") (pin "2") (pinfunction "2_2") (pintype "bidirectional"))
    )
    (net (code "108") (name "N_VW_OV") (class "Default")
      (node (ref "UNW") (pin "7") (pinfunction "OUTB_7") (pintype "output"))
      (node (ref "X-NORTH") (pin "1") (pinfunction "1_1") (pintype "bidirectional"))
    )
    (net (code "109") (name "N_VW_UV") (class "Default")
      (node (ref "UNW") (pin "1") (pinfunction "OUTA_1") (pintype "output"))
      (node (ref "X-NORTH") (pin "7") (pinfunction "7_7") (pintype "bidirectional"))
    )
    (net (code "110") (name "Net-(SENSORB-CMDN)") (class "Default")
      (node (ref "C61") (pin "1") (pinfunction "1_1") (pintype "passive"))
      (node (ref "SENSOR") (pin "F1") (pinfunction "CMDN_F1") (pintype "bidirectional"))
    )
    (net (code "111") (name "Net-(SENSORB-CMDP)") (class "Default")
      (node (ref "C22") (pin "2") (pinfunction "2_2") (pintype "passive"))
      (node (ref "SENSOR") (pin "F2") (pinfunction "CMDP_F2") (pintype "bidirectional"))
    )
    (net (code "112") (name "Net-(SENSORB-CMDP_COMP)") (class "Default")
      (node (ref "C28") (pin "2") (pinfunction "2_2") (pintype "passive"))
      (node (ref "SENSOR") (pin "H3") (pinfunction "CMDP_COMP_H3") (pintype "bidirectional"))
    )
    (net (code "113") (name "Net-(SENSORB-CMDP_COMP_INV)") (class "Default")
      (node (ref "C27") (pin "2") (pinfunction "2_2") (pintype "passive"))
      (node (ref "SENSOR") (pin "F3") (pinfunction "CMDP_COMP_INV_F3") (pintype "bidirectional"))
    )
    (net (code "114") (name "Net-(SENSORB-CMD_COLAMP)") (class "Default")
      (node (ref "C25") (pin "2") (pinfunction "2_2") (pintype "passive"))
      (node (ref "SENSOR") (pin "C6") (pinfunction "CMD_COLAMP_C6") (pintype "bidirectional"))
    )
    (net (code "115") (name "Net-(SENSORB-CMD_COL_LOAD)") (class "Default")
      (node (ref "C23") (pin "2") (pinfunction "2_2") (pintype "passive"))
      (node (ref "SENSOR") (pin "B1") (pinfunction "CMD_COL_LOAD_B1") (pintype "bidirectional"))
    )
    (net (code "116") (name "Net-(SENSORB-CMD_COL_PC)") (class "Default")
      (node (ref "C26") (pin "2") (pinfunction "2_2") (pintype "passive"))
      (node (ref "SENSOR") (pin "D1") (pinfunction "CMD_COL_PC_D1") (pintype "bidirectional"))
    )
    (net (code "117") (name "Net-(SENSORB-CMD_LVDS)") (class "Default")
      (node (ref "C62") (pin "1") (pinfunction "1_1") (pintype "passive"))
      (node (ref "SENSOR") (pin "C1") (pinfunction "CMD_LVDS_C1") (pintype "bidirectional"))
    )
    (net (code "118") (name "Net-(SENSORB-CMD_RAMP)") (class "Default")
      (node (ref "C24") (pin "2") (pinfunction "2_2") (pintype "passive"))
      (node (ref "SENSOR") (pin "B29") (pinfunction "CMD_RAMP_B29") (pintype "bidirectional"))
    )
    (net (code "119") (name "Net-(SENSORB-VBGAP)") (class "Default")
      (node (ref "C64") (pin "1") (pinfunction "1_1") (pintype "passive"))
      (node (ref "SENSOR") (pin "C29") (pinfunction "VBGAP_C29") (pintype "bidirectional"))
    )
    (net (code "120") (name "Net-(SENSORB-VCLAMP)") (class "Default")
      (node (ref "C63") (pin "1") (pinfunction "1_1") (pintype "passive"))
      (node (ref "SENSOR") (pin "D4") (pinfunction "VCLAMP_D4") (pintype "bidirectional"))
    )
    (net (code "121") (name "Net-(SENSORB-VCLAMP_ADC)") (class "Default")
      (node (ref "C60") (pin "1") (pinfunction "1_1") (pintype "passive"))
      (node (ref "SENSOR") (pin "G2") (pinfunction "VCLAMP_ADC_G2") (pintype "bidirectional"))
    )
    (net (code "122") (name "Net-(SENSORB-VPCH_H)") (class "Default")
      (node (ref "C71") (pin "1") (pinfunction "1_1") (pintype "passive"))
      (node (ref "SENSOR") (pin "C4") (pinfunction "VPCH_H_C4") (pintype "bidirectional"))
    )
    (net (code "123") (name "Net-(SENSORB-VPCH_L)") (class "Default")
      (node (ref "C14") (pin "1") (pinfunction "1_1") (pintype "passive"))
      (node (ref "SENSOR") (pin "A4") (pinfunction "VPCH_L_A4") (pintype "bidirectional"))
    )
    (net (code "124") (name "Net-(SENSORB-VREF)") (class "Default")
      (node (ref "C29") (pin "1") (pinfunction "1_1") (pintype "passive"))
      (node (ref "SENSOR") (pin "A3") (pinfunction "VREF_A3") (pintype "bidirectional"))
    )
    (net (code "125") (name "Net-(SENSORB-VREF_ADC)") (class "Default")
      (node (ref "C30") (pin "1") (pinfunction "1_1") (pintype "passive"))
      (node (ref "SENSOR") (pin "B3") (pinfunction "VREF_ADC_B3") (pintype "bidirectional"))
    )
    (net (code "126") (name "Net-(SENSORB-VRES_L)") (class "Default")
      (node (ref "C15") (pin "1") (pinfunction "1_1") (pintype "passive"))
      (node (ref "SENSOR") (pin "D5") (pinfunction "VRES_L_D5") (pintype "bidirectional"))
    )
    (net (code "127") (name "Net-(SENSORB-VTF_LOW0)") (class "Default")
      (node (ref "C18") (pin "1") (pinfunction "1_1") (pintype "passive"))
      (node (ref "SENSOR") (pin "C5") (pinfunction "VTF_LOW0_C5") (pintype "bidirectional"))
    )
    (net (code "128") (name "Net-(SENSORB-VTF_LOW1)") (class "Default")
      (node (ref "C19") (pin "1") (pinfunction "1_1") (pintype "passive"))
      (node (ref "SENSOR") (pin "D6") (pinfunction "VTF_LOW1_D6") (pintype "bidirectional"))
    )
    (net (code "129") (name "Net-(SENSORB-VTF_LOW2)") (class "Default")
      (node (ref "C20") (pin "1") (pinfunction "1_1") (pintype "passive"))
      (node (ref "SENSOR") (pin "B30") (pinfunction "VTF_LOW2_B30") (pintype "bidirectional"))
    )
    (net (code "130") (name "Net-(SENSORB-VTF_LOW3)") (class "Default")
      (node (ref "C21") (pin "1") (pinfunction "1_1") (pintype "passive"))
      (node (ref "SENSOR") (pin "C30") (pinfunction "VTF_LOW3_C30") (pintype "bidirectional"))
    )
    (net (code "131") (name "Net-(U3-ADJ)") (class "Default")
      (node (ref "R21") (pin "1") (pinfunction "1_1") (pintype "passive"))
      (node (ref "R22") (pin "2") (pinfunction "2_2") (pintype "passive"))
      (node (ref "U3") (pin "5") (pinfunction "ADJ_5") (pintype "input"))
    )
    (net (code "132") (name "Net-(UEP-WP)") (class "Default")
      (node (ref "R1X") (pin "2") (pinfunction "2_2") (pintype "passive"))
      (node (ref "R2X") (pin "1") (pinfunction "1_1") (pintype "passive"))
      (node (ref "UEP") (pin "7") (pinfunction "WP_7") (pintype "input"))
    )
    (net (code "133") (name "Net-(UNE-VINA+)") (class "Default")
      (node (ref "R7") (pin "2") (pinfunction "2_2") (pintype "passive"))
      (node (ref "R8") (pin "1") (pinfunction "1_1") (pintype "passive"))
      (node (ref "UNE") (pin "3") (pinfunction "VINA+_3") (pintype "input"))
    )
    (net (code "134") (name "Net-(UNE-VINB-)") (class "Default")
      (node (ref "R8") (pin "2") (pinfunction "2_2") (pintype "passive"))
      (node (ref "R9") (pin "1") (pinfunction "1_1") (pintype "passive"))
      (node (ref "UNE") (pin "6") (pinfunction "VINB-_6") (pintype "input"))
    )
    (net (code "135") (name "Net-(UNN-VINA+)") (class "Default")
      (node (ref "R4") (pin "2") (pinfunction "2_2") (pintype "passive"))
      (node (ref "R5") (pin "1") (pinfunction "1_1") (pintype "passive"))
      (node (ref "UNN") (pin "3") (pinfunction "VINA+_3") (pintype "input"))
    )
    (net (code "136") (name "Net-(UNN-VINB-)") (class "Default")
      (node (ref "R5") (pin "2") (pinfunction "2_2") (pintype "passive"))
      (node (ref "R6") (pin "1") (pinfunction "1_1") (pintype "passive"))
      (node (ref "UNN") (pin "6") (pinfunction "VINB-_6") (pintype "input"))
    )
    (net (code "137") (name "Net-(UNW-VINA+)") (class "Default")
      (node (ref "R1") (pin "2") (pinfunction "2_2") (pintype "passive"))
      (node (ref "R2") (pin "1") (pinfunction "1_1") (pintype "passive"))
      (node (ref "UNW") (pin "3") (pinfunction "VINA+_3") (pintype "input"))
    )
    (net (code "138") (name "Net-(UNW-VINB-)") (class "Default")
      (node (ref "R2") (pin "2") (pinfunction "2_2") (pintype "passive"))
      (node (ref "R3") (pin "1") (pinfunction "1_1") (pintype "passive"))
      (node (ref "UNW") (pin "6") (pinfunction "VINB-_6") (pintype "input"))
    )
    (net (code "139") (name "Net-(USE-VINA+)") (class "Default")
      (node (ref "R10") (pin "2") (pinfunction "2_2") (pintype "passive"))
      (node (ref "R11") (pin "1") (pinfunction "1_1") (pintype "passive"))
      (node (ref "USE") (pin "3") (pinfunction "VINA+_3") (pintype "input"))
    )
    (net (code "140") (name "Net-(USE-VINB-)") (class "Default")
      (node (ref "R11") (pin "2") (pinfunction "2_2") (pintype "passive"))
      (node (ref "R12") (pin "1") (pinfunction "1_1") (pintype "passive"))
      (node (ref "USE") (pin "6") (pinfunction "VINB-_6") (pintype "input"))
    )
    (net (code "141") (name "Net-(USS-VINA+)") (class "Default")
      (node (ref "R13") (pin "2") (pinfunction "2_2") (pintype "passive"))
      (node (ref "R14") (pin "1") (pinfunction "1_1") (pintype "passive"))
      (node (ref "USS") (pin "3") (pinfunction "VINA+_3") (pintype "input"))
    )
    (net (code "142") (name "Net-(USS-VINB-)") (class "Default")
      (node (ref "R14") (pin "2") (pinfunction "2_2") (pintype "passive"))
      (node (ref "R15") (pin "1") (pinfunction "1_1") (pintype "passive"))
      (node (ref "USS") (pin "6") (pinfunction "VINB-_6") (pintype "input"))
    )
    (net (code "143") (name "Net-(USW-VINA+)") (class "Default")
      (node (ref "R16") (pin "2") (pinfunction "2_2") (pintype "passive"))
      (node (ref "R17") (pin "1") (pinfunction "1_1") (pintype "passive"))
      (node (ref "USW") (pin "3") (pinfunction "VINA+_3") (pintype "input"))
    )
    (net (code "144") (name "Net-(USW-VINB-)") (class "Default")
      (node (ref "R17") (pin "2") (pinfunction "2_2") (pintype "passive"))
      (node (ref "R18") (pin "1") (pinfunction "1_1") (pintype "passive"))
      (node (ref "USW") (pin "6") (pinfunction "VINB-_6") (pintype "input"))
    )
    (net (code "145") (name "S00_N") (class "Default")
      (node (ref "X-SOUTH") (pin "16") (pinfunction "16_16") (pintype "bidirectional"))
    )
    (net (code "146") (name "S00_P") (class "Default")
      (node (ref "X-SOUTH") (pin "14") (pinfunction "14_14") (pintype "bidirectional"))
    )
    (net (code "147") (name "S01_N") (class "Default")
      (node (ref "X-SOUTH") (pin "17") (pinfunction "17_17") (pintype "bidirectional"))
    )
    (net (code "148") (name "S01_P") (class "Default")
      (node (ref "X-SOUTH") (pin "15") (pinfunction "15_15") (pintype "bidirectional"))
    )
    (net (code "149") (name "S02_N") (class "Default")
      (node (ref "X-SOUTH") (pin "22") (pinfunction "22_22") (pintype "bidirectional"))
    )
    (net (code "150") (name "S02_P") (class "Default")
      (node (ref "X-SOUTH") (pin "20") (pinfunction "20_20") (pintype "bidirectional"))
    )
    (net (code "151") (name "S03_N") (class "Default")
      (node (ref "X-SOUTH") (pin "23") (pinfunction "23_23") (pintype "bidirectional"))
    )
    (net (code "152") (name "S03_P") (class "Default")
      (node (ref "X-SOUTH") (pin "21") (pinfunction "21_21") (pintype "bidirectional"))
    )
    (net (code "153") (name "S04_N") (class "Default")
      (node (ref "SENSOR") (pin "C24") (pinfunction "OUT32_N_C24") (pintype "output"))
      (node (ref "X-SOUTH") (pin "28") (pinfunction "28_28") (pintype "bidirectional"))
    )
    (net (code "154") (name "S04_P") (class "Default")
      (node (ref "SENSOR") (pin "C25") (pinfunction "OUT32_P_C25") (pintype "output"))
      (node (ref "X-SOUTH") (pin "26") (pinfunction "26_26") (pintype "bidirectional"))
    )
    (net (code "155") (name "S05_N") (class "Default")
      (node (ref "X-SOUTH") (pin "29") (pinfunction "29_29") (pintype "bidirectional"))
    )
    (net (code "156") (name "S05_P") (class "Default")
      (node (ref "X-SOUTH") (pin "27") (pinfunction "27_27") (pintype "bidirectional"))
    )
    (net (code "157") (name "S06_N") (class "Default")
      (node (ref "SENSOR") (pin "D23") (pinfunction "OUT30_N_D23") (pintype "output"))
      (node (ref "X-SOUTH") (pin "34") (pinfunction "34_34") (pintype "bidirectional"))
    )
    (net (code "158") (name "S06_P") (class "Default")
      (node (ref "SENSOR") (pin "D24") (pinfunction "OUT30_P_D24") (pintype "output"))
      (node (ref "X-SOUTH") (pin "32") (pinfunction "32_32") (pintype "bidirectional"))
    )
    (net (code "159") (name "S07_N") (class "Default")
      (node (ref "SENSOR") (pin "B24") (pinfunction "OUT31_N_B24") (pintype "output"))
      (node (ref "X-SOUTH") (pin "35") (pinfunction "35_35") (pintype "bidirectional"))
    )
    (net (code "160") (name "S07_P") (class "Default")
      (node (ref "SENSOR") (pin "B25") (pinfunction "OUT31_P_B25") (pintype "output"))
      (node (ref "X-SOUTH") (pin "33") (pinfunction "33_33") (pintype "bidirectional"))
    )
    (net (code "161") (name "S08_N") (class "Default")
      (node (ref "SENSOR") (pin "D21") (pinfunction "OUT27_N_D21") (pintype "output"))
      (node (ref "X-SOUTH") (pin "40") (pinfunction "40_40") (pintype "bidirectional"))
    )
    (net (code "162") (name "S08_P") (class "Default")
      (node (ref "SENSOR") (pin "D22") (pinfunction "OUT27_P_D22") (pintype "output"))
      (node (ref "X-SOUTH") (pin "38") (pinfunction "38_38") (pintype "bidirectional"))
    )
    (net (code "163") (name "S09_N") (class "Default")
      (node (ref "SENSOR") (pin "A23") (pinfunction "OUT29_N_A23") (pintype "output"))
      (node (ref "X-SOUTH") (pin "41") (pinfunction "41_41") (pintype "bidirectional"))
    )
    (net (code "164") (name "S09_P") (class "Default")
      (node (ref "SENSOR") (pin "A24") (pinfunction "OUT29_P_A24") (pintype "output"))
      (node (ref "X-SOUTH") (pin "39") (pinfunction "39_39") (pintype "bidirectional"))
    )
    (net (code "165") (name "S10_N") (class "Default")
      (node (ref "SENSOR") (pin "C21") (pinfunction "OUT28_N_C21") (pintype "output"))
      (node (ref "X-SOUTH") (pin "46") (pinfunction "46_46") (pintype "bidirectional"))
    )
    (net (code "166") (name "S10_P") (class "Default")
      (node (ref "SENSOR") (pin "C22") (pinfunction "OUT28_P_C22") (pintype "output"))
      (node (ref "X-SOUTH") (pin "44") (pinfunction "44_44") (pintype "bidirectional"))
    )
    (net (code "167") (name "S11_N") (class "Default")
      (node (ref "SENSOR") (pin "B20") (pinfunction "OUT26_N_B20") (pintype "output"))
      (node (ref "X-SOUTH") (pin "47") (pinfunction "47_47") (pintype "bidirectional"))
    )
    (net (code "168") (name "S11_P") (class "Default")
      (node (ref "SENSOR") (pin "B21") (pinfunction "OUT26_P_B21") (pintype "output"))
      (node (ref "X-SOUTH") (pin "45") (pinfunction "45_45") (pintype "bidirectional"))
    )
    (net (code "169") (name "S12_N") (class "Default")
      (node (ref "SENSOR") (pin "D19") (pinfunction "OUT24_N_D19") (pintype "output"))
      (node (ref "X-SOUTH") (pin "52") (pinfunction "52_52") (pintype "bidirectional"))
    )
    (net (code "170") (name "S12_P") (class "Default")
      (node (ref "SENSOR") (pin "D20") (pinfunction "OUT24_P_D20") (pintype "output"))
      (node (ref "X-SOUTH") (pin "50") (pinfunction "50_50") (pintype "bidirectional"))
    )
    (net (code "171") (name "S13_N") (class "Default")
      (node (ref "SENSOR") (pin "A19") (pinfunction "OUT23_N_A19") (pintype "output"))
      (node (ref "X-SOUTH") (pin "53") (pinfunction "53_53") (pintype "bidirectional"))
    )
    (net (code "172") (name "S13_P") (class "Default")
      (node (ref "SENSOR") (pin "A20") (pinfunction "OUT23_P_A20") (pintype "output"))
      (node (ref "X-SOUTH") (pin "51") (pinfunction "51_51") (pintype "bidirectional"))
    )
    (net (code "173") (name "S14_N") (class "Default")
      (node (ref "SENSOR") (pin "C19") (pinfunction "OUT25_N_C19") (pintype "output"))
      (node (ref "X-SOUTH") (pin "58") (pinfunction "58_58") (pintype "bidirectional"))
    )
    (net (code "174") (name "S14_P") (class "Default")
      (node (ref "SENSOR") (pin "C20") (pinfunction "OUT25_P_C20") (pintype "output"))
      (node (ref "X-SOUTH") (pin "56") (pinfunction "56_56") (pintype "bidirectional"))
    )
    (net (code "175") (name "S15_N") (class "Default")
      (node (ref "SENSOR") (pin "B18") (pinfunction "OUT22_N_B18") (pintype "output"))
      (node (ref "X-SOUTH") (pin "59") (pinfunction "59_59") (pintype "bidirectional"))
    )
    (net (code "176") (name "S15_P") (class "Default")
      (node (ref "SENSOR") (pin "B19") (pinfunction "OUT22_P_B19") (pintype "output"))
      (node (ref "X-SOUTH") (pin "57") (pinfunction "57_57") (pintype "bidirectional"))
    )
    (net (code "177") (name "S16_N") (class "Default")
      (node (ref "SENSOR") (pin "C17") (pinfunction "OUT21_N_C17") (pintype "output"))
      (node (ref "X-SOUTH") (pin "64") (pinfunction "64_64") (pintype "bidirectional"))
    )
    (net (code "178") (name "S16_P") (class "Default")
      (node (ref "SENSOR") (pin "C18") (pinfunction "OUT21_P_C18") (pintype "output"))
      (node (ref "X-SOUTH") (pin "62") (pinfunction "62_62") (pintype "bidirectional"))
    )
    (net (code "179") (name "S17_N") (class "Default")
      (node (ref "SENSOR") (pin "A17") (pinfunction "OUT19_N_A17") (pintype "output"))
      (node (ref "X-SOUTH") (pin "65") (pinfunction "65_65") (pintype "bidirectional"))
    )
    (net (code "180") (name "S17_P") (class "Default")
      (node (ref "SENSOR") (pin "A18") (pinfunction "OUT19_P_A18") (pintype "output"))
      (node (ref "X-SOUTH") (pin "63") (pinfunction "63_63") (pintype "bidirectional"))
    )
    (net (code "181") (name "S18_N") (class "Default")
      (node (ref "SENSOR") (pin "D17") (pinfunction "OUT20_N_D17") (pintype "output"))
      (node (ref "X-SOUTH") (pin "70") (pinfunction "70_70") (pintype "bidirectional"))
    )
    (net (code "182") (name "S18_P") (class "Default")
      (node (ref "SENSOR") (pin "D18") (pinfunction "OUT20_P_D18") (pintype "output"))
      (node (ref "X-SOUTH") (pin "68") (pinfunction "68_68") (pintype "bidirectional"))
    )
    (net (code "183") (name "S19_N") (class "Default")
      (node (ref "SENSOR") (pin "B16") (pinfunction "OUT18_N_B16") (pintype "output"))
      (node (ref "X-SOUTH") (pin "71") (pinfunction "71_71") (pintype "bidirectional"))
    )
    (net (code "184") (name "S19_P") (class "Default")
      (node (ref "SENSOR") (pin "B17") (pinfunction "OUT18_P_B17") (pintype "output"))
      (node (ref "X-SOUTH") (pin "69") (pinfunction "69_69") (pintype "bidirectional"))
    )
    (net (code "185") (name "S20_N") (class "Default")
      (node (ref "SENSOR") (pin "D15") (pinfunction "OUT17_N_D15") (pintype "output"))
      (node (ref "X-SOUTH") (pin "76") (pinfunction "76_76") (pintype "bidirectional"))
    )
    (net (code "186") (name "S20_P") (class "Default")
      (node (ref "SENSOR") (pin "D16") (pinfunction "OUT17_P_D16") (pintype "output"))
      (node (ref "X-SOUTH") (pin "74") (pinfunction "74_74") (pintype "bidirectional"))
    )
    (net (code "187") (name "S21_N") (class "Default")
      (node (ref "SENSOR") (pin "B14") (pinfunction "OUT16_N_B14") (pintype "output"))
      (node (ref "X-SOUTH") (pin "77") (pinfunction "77_77") (pintype "bidirectional"))
    )
    (net (code "188") (name "S21_P") (class "Default")
      (node (ref "SENSOR") (pin "B15") (pinfunction "OUT16_P_B15") (pintype "output"))
      (node (ref "X-SOUTH") (pin "75") (pinfunction "75_75") (pintype "bidirectional"))
    )
    (net (code "189") (name "S22_N") (class "Default")
      (node (ref "SENSOR") (pin "D13") (pinfunction "OUT15_N_D13") (pintype "output"))
      (node (ref "X-SOUTH") (pin "82") (pinfunction "82_82") (pintype "bidirectional"))
    )
    (net (code "190") (name "S22_P") (class "Default")
      (node (ref "SENSOR") (pin "D14") (pinfunction "OUT15_P_D14") (pintype "output"))
      (node (ref "X-SOUTH") (pin "80") (pinfunction "80_80") (pintype "bidirectional"))
    )
    (net (code "191") (name "S23_N") (class "Default")
      (node (ref "SENSOR") (pin "A13") (pinfunction "OUT13_N_A13") (pintype "output"))
      (node (ref "X-SOUTH") (pin "83") (pinfunction "83_83") (pintype "bidirectional"))
    )
    (net (code "192") (name "S23_P") (class "Default")
      (node (ref "SENSOR") (pin "A14") (pinfunction "OUT13_P_A14") (pintype "output"))
      (node (ref "X-SOUTH") (pin "81") (pinfunction "81_81") (pintype "bidirectional"))
    )
    (net (code "193") (name "S24_N") (class "Default")
      (node (ref "SENSOR") (pin "C13") (pinfunction "OUT14_N_C13") (pintype "output"))
      (node (ref "X-SOUTH") (pin "88") (pinfunction "88_88") (pintype "bidirectional"))
    )
    (net (code "194") (name "S24_P") (class "Default")
      (node (ref "SENSOR") (pin "C14") (pinfunction "OUT14_P_C14") (pintype "output"))
      (node (ref "X-SOUTH") (pin "86") (pinfunction "86_86") (pintype "bidirectional"))
    )
    (net (code "195") (name "S25_N") (class "Default")
      (node (ref "SENSOR") (pin "B12") (pinfunction "OUT12_N_B12") (pintype "output"))
      (node (ref "X-SOUTH") (pin "89") (pinfunction "89_89") (pintype "bidirectional"))
    )
    (net (code "196") (name "S25_P") (class "Default")
      (node (ref "SENSOR") (pin "B13") (pinfunction "OUT12_P_B13") (pintype "output"))
      (node (ref "X-SOUTH") (pin "87") (pinfunction "87_87") (pintype "bidirectional"))
    )
    (net (code "197") (name "S26_N") (class "Default")
      (node (ref "SENSOR") (pin "D11") (pinfunction "OUT10_N_D11") (pintype "output"))
      (node (ref "X-SOUTH") (pin "94") (pinfunction "94_94") (pintype "bidirectional"))
    )
    (net (code "198") (name "S26_P") (class "Default")
      (node (ref "SENSOR") (pin "D12") (pinfunction "OUT10_P_D12") (pintype "output"))
      (node (ref "X-SOUTH") (pin "92") (pinfunction "92_92") (pintype "bidirectional"))
    )
    (net (code "199") (name "S27_N") (class "Default")
      (node (ref "SENSOR") (pin "A11") (pinfunction "OUT9_N_A11") (pintype "output"))
      (node (ref "X-SOUTH") (pin "95") (pinfunction "95_95") (pintype "bidirectional"))
    )
    (net (code "200") (name "S27_P") (class "Default")
      (node (ref "SENSOR") (pin "A12") (pinfunction "OUT9_P_A12") (pintype "output"))
      (node (ref "X-SOUTH") (pin "93") (pinfunction "93_93") (pintype "bidirectional"))
    )
    (net (code "201") (name "S28_N") (class "Default")
      (node (ref "SENSOR") (pin "C11") (pinfunction "OUT11_N_C11") (pintype "output"))
      (node (ref "X-SOUTH") (pin "100") (pinfunction "100_100") (pintype "bidirectional"))
    )
    (net (code "202") (name "S28_P") (class "Default")
      (node (ref "SENSOR") (pin "C12") (pinfunction "OUT11_P_C12") (pintype "output"))
      (node (ref "X-SOUTH") (pin "98") (pinfunction "98_98") (pintype "bidirectional"))
    )
    (net (code "203") (name "S29_N") (class "Default")
      (node (ref "SENSOR") (pin "B10") (pinfunction "OUT8_N_B10") (pintype "output"))
      (node (ref "X-SOUTH") (pin "101") (pinfunction "101_101") (pintype "bidirectional"))
    )
    (net (code "204") (name "S29_P") (class "Default")
      (node (ref "SENSOR") (pin "B11") (pinfunction "OUT8_P_B11") (pintype "output"))
      (node (ref "X-SOUTH") (pin "99") (pinfunction "99_99") (pintype "bidirectional"))
    )
    (net (code "205") (name "S30_N") (class "Default")
      (node (ref "SENSOR") (pin "C9") (pinfunction "OUT7_N_C9") (pintype "output"))
      (node (ref "X-SOUTH") (pin "106") (pinfunction "106_106") (pintype "bidirectional"))
    )
    (net (code "206") (name "S30_P") (class "Default")
      (node (ref "SENSOR") (pin "C10") (pinfunction "OUT7_P_C10") (pintype "output"))
      (node (ref "X-SOUTH") (pin "104") (pinfunction "104_104") (pintype "bidirectional"))
    )
    (net (code "207") (name "S31_N") (class "Default")
      (node (ref "SENSOR") (pin "B8") (pinfunction "OUT5_N_B8") (pintype "output"))
      (node (ref "X-SOUTH") (pin "107") (pinfunction "107_107") (pintype "bidirectional"))
    )
    (net (code "208") (name "S31_P") (class "Default")
      (node (ref "SENSOR") (pin "B9") (pinfunction "OUT5_P_B9") (pintype "output"))
      (node (ref "X-SOUTH") (pin "105") (pinfunction "105_105") (pintype "bidirectional"))
    )
    (net (code "209") (name "S32_N") (class "Default")
      (node (ref "SENSOR") (pin "D9") (pinfunction "OUT6_N_D9") (pintype "output"))
      (node (ref "X-SOUTH") (pin "112") (pinfunction "112_112") (pintype "bidirectional"))
    )
    (net (code "210") (name "S32_P") (class "Default")
      (node (ref "SENSOR") (pin "D10") (pinfunction "OUT6_P_D10") (pintype "output"))
      (node (ref "X-SOUTH") (pin "110") (pinfunction "110_110") (pintype "bidirectional"))
    )
    (net (code "211") (name "S33_N") (class "Default")
      (node (ref "SENSOR") (pin "A7") (pinfunction "OUT2_N_A7") (pintype "output"))
      (node (ref "X-SOUTH") (pin "113") (pinfunction "113_113") (pintype "bidirectional"))
    )
    (net (code "212") (name "S33_P") (class "Default")
      (node (ref "SENSOR") (pin "A8") (pinfunction "OUT2_P_A8") (pintype "output"))
      (node (ref "X-SOUTH") (pin "111") (pinfunction "111_111") (pintype "bidirectional"))
    )
    (net (code "213") (name "S34_N") (class "Default")
      (node (ref "SENSOR") (pin "C7") (pinfunction "OUT4_N_C7") (pintype "output"))
      (node (ref "X-SOUTH") (pin "118") (pinfunction "118_118") (pintype "bidirectional"))
    )
    (net (code "214") (name "S34_P") (class "Default")
      (node (ref "SENSOR") (pin "C8") (pinfunction "OUT4_P_C8") (pintype "output"))
      (node (ref "X-SOUTH") (pin "116") (pinfunction "116_116") (pintype "bidirectional"))
    )
    (net (code "215") (name "S35_N") (class "Default")
      (node (ref "SENSOR") (pin "B6") (pinfunction "OUT1_N_B6") (pintype "output"))
      (node (ref "X-SOUTH") (pin "119") (pinfunction "119_119") (pintype "bidirectional"))
    )
    (net (code "216") (name "S35_P") (class "Default")
      (node (ref "SENSOR") (pin "B7") (pinfunction "OUT1_P_B7") (pintype "output"))
      (node (ref "X-SOUTH") (pin "117") (pinfunction "117_117") (pintype "bidirectional"))
    )
    (net (code "217") (name "S36_N") (class "Default")
      (node (ref "SENSOR") (pin "D7") (pinfunction "OUT3_N_D7") (pintype "output"))
      (node (ref "X-SOUTH") (pin "124") (pinfunction "124_124") (pintype "bidirectional"))
    )
    (net (code "218") (name "S36_P") (class "Default")
      (node (ref "SENSOR") (pin "D8") (pinfunction "OUT3_P_D8") (pintype "output"))
      (node (ref "X-SOUTH") (pin "122") (pinfunction "122_122") (pintype "bidirectional"))
    )
    (net (code "219") (name "S37_N") (class "Default")
      (node (ref "SENSOR") (pin "A5") (pinfunction "OUTCTR_N_A5") (pintype "output"))
      (node (ref "X-SOUTH") (pin "125") (pinfunction "125_125") (pintype "bidirectional"))
    )
    (net (code "220") (name "S37_P") (class "Default")
      (node (ref "SENSOR") (pin "A6") (pinfunction "OUTCTR_P_A6") (pintype "output"))
      (node (ref "X-SOUTH") (pin "123") (pinfunction "123_123") (pintype "bidirectional"))
    )
    (net (code "221") (name "S38_N") (class "Default")
      (node (ref "X-SOUTH") (pin "130") (pinfunction "130_130") (pintype "bidirectional"))
    )
    (net (code "222") (name "S38_P") (class "Default")
      (node (ref "X-SOUTH") (pin "128") (pinfunction "128_128") (pintype "bidirectional"))
    )
    (net (code "223") (name "S39_N") (class "Default")
      (node (ref "U3") (pin "6") (pinfunction "EN_6") (pintype "input"))
      (node (ref "X-SOUTH") (pin "131") (pinfunction "131_131") (pintype "bidirectional"))
    )
    (net (code "224") (name "S39_P") (class "Default")
      (node (ref "X-SOUTH") (pin "129") (pinfunction "129_129") (pintype "bidirectional"))
    )
    (net (code "225") (name "SPI_CLK") (class "Default")
      (node (ref "SENSOR") (pin "H29") (pinfunction "SPI_CLK_H29") (pintype "input"))
      (node (ref "U4") (pin "6") (pinfunction "1A1_6") (pintype "output"))
    )
    (net (code "226") (name "SPI_EN") (class "Default")
      (node (ref "SENSOR") (pin "F28") (pinfunction "SPI_EN_F28") (pintype "input"))
      (node (ref "U6") (pin "9") (pinfunction "B4_9") (pintype "bidirectional"))
    )
    (net (code "227") (name "SPI_IN") (class "Default")
      (node (ref "SENSOR") (pin "E28") (pinfunction "SPI_IN_E28") (pintype "input"))
      (node (ref "U4") (pin "7") (pinfunction "1A2_7") (pintype "output"))
    )
    (net (code "228") (name "SPI_OUT") (class "Default")
      (node (ref "SENSOR") (pin "G28") (pinfunction "SPI_OUT_G28") (pintype "output"))
      (node (ref "U4") (pin "8") (pinfunction "2A1_8") (pintype "output"))
    )
    (net (code "229") (name "SYS_RES_N") (class "Default")
      (node (ref "SENSOR") (pin "F30") (pinfunction "SYS_RES_N_F30") (pintype "input"))
      (node (ref "U5") (pin "10") (pinfunction "B3_10") (pintype "bidirectional"))
    )
    (net (code "230") (name "S_CHK_V") (class "Default")
      (node (ref "C5") (pin "1") (pinfunction "1_1") (pintype "passive"))
      (node (ref "C6") (pin "1") (pinfunction "1_1") (pintype "passive"))
      (node (ref "C7") (pin "1") (pinfunction "1_1") (pintype "passive"))
      (node (ref "R20") (pin "1") (pinfunction "1_1") (pintype "passive"))
      (node (ref "TP3") (pin "TP") (pinfunction "TP_TP") (pintype "input"))
      (node (ref "USE") (pin "8") (pinfunction "VDD_8") (pintype "power_in"))
      (node (ref "USS") (pin "8") (pinfunction "VDD_8") (pintype "power_in"))
      (node (ref "USW") (pin "8") (pinfunction "VDD_8") (pintype "power_in"))
      (node (ref "X-SOUTH") (pin "10") (pinfunction "10_10") (pintype "bidirectional"))
      (node (ref "X-SOUTH") (pin "8") (pinfunction "8_8") (pintype "bidirectional"))
    )
    (net (code "231") (name "S_I2C_V") (class "Default")
      (node (ref "X-SOUTH") (pin "135") (pinfunction "135_135") (pintype "bidirectional"))
      (node (ref "X-SOUTH") (pin "137") (pinfunction "137_137") (pintype "bidirectional"))
    )
    (net (code "232") (name "S_REF") (class "Default")
      (node (ref "R20") (pin "2") (pinfunction "2_2") (pintype "passive"))
      (node (ref "TP4") (pin "TP") (pinfunction "TP_TP") (pintype "input"))
      (node (ref "U2") (pin "1") (pinfunction "CATHODE_1") (pintype "output"))
      (node (ref "U2") (pin "3") (pinfunction "REF_3") (pintype "input"))
      (node (ref "USE") (pin "2") (pinfunction "VINA-_2") (pintype "input"))
      (node (ref "USE") (pin "5") (pinfunction "VINB+_5") (pintype "input"))
      (node (ref "USS") (pin "2") (pinfunction "VINA-_2") (pintype "input"))
      (node (ref "USS") (pin "5") (pinfunction "VINB+_5") (pintype "input"))
      (node (ref "USW") (pin "2") (pinfunction "VINA-_2") (pintype "input"))
      (node (ref "USW") (pin "5") (pinfunction "VINB+_5") (pintype "input"))
    )
    (net (code "233") (name "S_SCK") (class "Default")
      (node (ref "X-SOUTH") (pin "144") (pinfunction "144_144") (pintype "bidirectional"))
    )
    (net (code "234") (name "S_SCL") (class "Default")
      (node (ref "X-SOUTH") (pin "143") (pinfunction "143_143") (pintype "bidirectional"))
    )
    (net (code "235") (name "S_SDA") (class "Default")
      (node (ref "X-SOUTH") (pin "141") (pinfunction "141_141") (pintype "bidirectional"))
    )
    (net (code "236") (name "S_SDI") (class "Default")
      (node (ref "X-SOUTH") (pin "140") (pinfunction "140_140") (pintype "bidirectional"))
    )
    (net (code "237") (name "S_SDO") (class "Default")
      (node (ref "X-SOUTH") (pin "142") (pinfunction "142_142") (pintype "bidirectional"))
    )
    (net (code "238") (name "S_SPI_V") (class "Default")
      (node (ref "X-SOUTH") (pin "134") (pinfunction "134_134") (pintype "bidirectional"))
      (node (ref "X-SOUTH") (pin "136") (pinfunction "136_136") (pintype "bidirectional"))
    )
    (net (code "239") (name "S_VE") (class "Default")
      (node (ref "X-SOUTH") (pin "13") (pinfunction "13_13") (pintype "bidirectional"))
      (node (ref "X-SOUTH") (pin "19") (pinfunction "19_19") (pintype "bidirectional"))
      (node (ref "X-SOUTH") (pin "25") (pinfunction "25_25") (pintype "bidirectional"))
      (node (ref "X-SOUTH") (pin "31") (pinfunction "31_31") (pintype "bidirectional"))
      (node (ref "X-SOUTH") (pin "37") (pinfunction "37_37") (pintype "bidirectional"))
    )
    (net (code "240") (name "S_VE_CV") (class "Default")
      (node (ref "C11") (pin "1") (pinfunction "1_1") (pintype "passive"))
      (node (ref "R10") (pin "1") (pinfunction "1_1") (pintype "passive"))
      (node (ref "X-SOUTH") (pin "2") (pinfunction "2_2") (pintype "bidirectional"))
    )
    (net (code "241") (name "S_VE_OV") (class "Default")
      (node (ref "USE") (pin "7") (pinfunction "OUTB_7") (pintype "output"))
      (node (ref "X-SOUTH") (pin "1") (pinfunction "1_1") (pintype "bidirectional"))
    )
    (net (code "242") (name "S_VE_UV") (class "Default")
      (node (ref "USE") (pin "1") (pinfunction "OUTA_1") (pintype "output"))
      (node (ref "X-SOUTH") (pin "7") (pinfunction "7_7") (pintype "bidirectional"))
    )
    (net (code "243") (name "S_VS") (class "Default")
      (node (ref "C45") (pin "1") (pinfunction "1_1") (pintype "passive"))
      (node (ref "C46") (pin "1") (pinfunction "1_1") (pintype "passive"))
      (node (ref "C47") (pin "1") (pinfunction "1_1") (pintype "passive"))
      (node (ref "C48") (pin "1") (pinfunction "1_1") (pintype "passive"))
      (node (ref "C49") (pin "1") (pinfunction "1_1") (pintype "passive"))
      (node (ref "C72") (pin "1") (pinfunction "1_1") (pintype "passive"))
      (node (ref "C73") (pin "1") (pinfunction "1_1") (pintype "passive"))
      (node (ref "C74") (pin "1") (pinfunction "1_1") (pintype "passive"))
      (node (ref "C81") (pin "1") (pinfunction "1_1") (pintype "passive"))
      (node (ref "C82") (pin "1") (pinfunction "1_1") (pintype "passive"))
      (node (ref "C83") (pin "1") (pinfunction "1_1") (pintype "passive"))
      (node (ref "SENSOR") (pin "A30") (pinfunction "VDD_PIX_A30") (pintype "power_in"))
      (node (ref "SENSOR") (pin "D28") (pinfunction "VDD_PIX_D28") (pintype "power_in"))
      (node (ref "SENSOR") (pin "D30") (pinfunction "VDD_PIX_D30") (pintype "power_in"))
      (node (ref "SENSOR") (pin "G1") (pinfunction "VDD_PIX_G1") (pintype "power_in"))
      (node (ref "SENSOR") (pin "H28") (pinfunction "VDD_PIX_H28") (pintype "power_in"))
      (node (ref "TP6") (pin "TP") (pinfunction "TP_TP") (pintype "input"))
      (node (ref "X-SOUTH") (pin "49") (pinfunction "49_49") (pintype "bidirectional"))
      (node (ref "X-SOUTH") (pin "55") (pinfunction "55_55") (pintype "bidirectional"))
      (node (ref "X-SOUTH") (pin "61") (pinfunction "61_61") (pintype "bidirectional"))
      (node (ref "X-SOUTH") (pin "67") (pinfunction "67_67") (pintype "bidirectional"))
      (node (ref "X-SOUTH") (pin "73") (pinfunction "73_73") (pintype "bidirectional"))
      (node (ref "X-SOUTH") (pin "79") (pinfunction "79_79") (pintype "bidirectional"))
      (node (ref "X-SOUTH") (pin "85") (pinfunction "85_85") (pintype "bidirectional"))
      (node (ref "X-SOUTH") (pin "91") (pinfunction "91_91") (pintype "bidirectional"))
      (node (ref "X-SOUTH") (pin "97") (pinfunction "97_97") (pintype "bidirectional"))
    )
    (net (code "244") (name "S_VS_CV") (class "Default")
      (node (ref "C12") (pin "1") (pinfunction "1_1") (pintype "passive"))
      (node (ref "R13") (pin "1") (pinfunction "1_1") (pintype "passive"))
      (node (ref "X-SOUTH") (pin "4") (pinfunction "4_4") (pintype "bidirectional"))
    )
    (net (code "245") (name "S_VS_OV") (class "Default")
      (node (ref "USS") (pin "7") (pinfunction "OUTB_7") (pintype "output"))
      (node (ref "X-SOUTH") (pin "3") (pinfunction "3_3") (pintype "bidirectional"))
    )
    (net (code "246") (name "S_VS_UV") (class "Default")
      (node (ref "USS") (pin "1") (pinfunction "OUTA_1") (pintype "output"))
      (node (ref "X-SOUTH") (pin "9") (pinfunction "9_9") (pintype "bidirectional"))
    )
    (net (code "247") (name "S_VW") (class "Default")
      (node (ref "C90") (pin "1") (pinfunction "1_1") (pintype "passive"))
      (node (ref "U3") (pin "1") (pinfunction "BIAS_1") (pintype "power_in"))
      (node (ref "U3") (pin "3") (pinfunction "IN_3") (pintype "power_in"))
      (node (ref "X-SOUTH") (pin "109") (pinfunction "109_109") (pintype "bidirectional"))
      (node (ref "X-SOUTH") (pin "115") (pinfunction "115_115") (pintype "bidirectional"))
      (node (ref "X-SOUTH") (pin "121") (pinfunction "121_121") (pintype "bidirectional"))
      (node (ref "X-SOUTH") (pin "127") (pinfunction "127_127") (pintype "bidirectional"))
      (node (ref "X-SOUTH") (pin "133") (pinfunction "133_133") (pintype "bidirectional"))
    )
    (net (code "248") (name "S_VW_CV") (class "Default")
      (node (ref "C13") (pin "1") (pinfunction "1_1") (pintype "passive"))
      (node (ref "R16") (pin "1") (pinfunction "1_1") (pintype "passive"))
      (node (ref "X-SOUTH") (pin "6") (pinfunction "6_6") (pintype "bidirectional"))
    )
    (net (code "249") (name "S_VW_OV") (class "Default")
      (node (ref "USW") (pin "7") (pinfunction "OUTB_7") (pintype "output"))
      (node (ref "X-SOUTH") (pin "5") (pinfunction "5_5") (pintype "bidirectional"))
    )
    (net (code "250") (name "S_VW_UV") (class "Default")
      (node (ref "USW") (pin "1") (pinfunction "OUTA_1") (pintype "output"))
      (node (ref "X-SOUTH") (pin "11") (pinfunction "11_11") (pintype "bidirectional"))
    )
    (net (code "251") (name "TDIG1") (class "Default")
      (node (ref "SENSOR") (pin "G27") (pinfunction "TDIG1_G27") (pintype "output"))
      (node (ref "U5") (pin "9") (pinfunction "B4_9") (pintype "bidirectional"))
    )
    (net (code "252") (name "TDIG2") (class "Default")
      (node (ref "SENSOR") (pin "G26") (pinfunction "TDIG2_G26") (pintype "output"))
      (node (ref "U6") (pin "11") (pinfunction "B2_11") (pintype "bidirectional"))
    )
    (net (code "253") (name "T_EXP1") (class "Default")
      (node (ref "SENSOR") (pin "H30") (pinfunction "T_EXP1_H30") (pintype "input"))
      (node (ref "U5") (pin "12") (pinfunction "B1_12") (pintype "bidirectional"))
    )
    (net (code "254") (name "T_EXP2") (class "Default")
      (node (ref "SENSOR") (pin "E29") (pinfunction "T_EXP2_E29") (pintype "input"))
      (node (ref "U6") (pin "10") (pinfunction "B3_10") (pintype "bidirectional"))
    )
    (net (code "255") (name "VRAMP1") (class "Default")
      (node (ref "C16") (pin "1") (pinfunction "1_1") (pintype "passive"))
      (node (ref "R23") (pin "1") (pinfunction "1_1") (pintype "passive"))
      (node (ref "SENSOR") (pin "G29") (pinfunction "VRAMP1_G29") (pintype "bidirectional"))
    )
    (net (code "256") (name "VRAMP2") (class "Default")
      (node (ref "C17") (pin "1") (pinfunction "1_1") (pintype "passive"))
      (node (ref "R23") (pin "2") (pinfunction "2_2") (pintype "passive"))
      (node (ref "SENSOR") (pin "F29") (pinfunction "VRAMP2_F29") (pintype "bidirectional"))
    )
    (net (code "257") (name "VTREF") (class "Default")
      (node (ref "C65") (pin "1") (pinfunction "1_1") (pintype "passive"))
      (node (ref "C91") (pin "2") (pinfunction "2_2") (pintype "passive"))
      (node (ref "R21") (pin "2") (pinfunction "2_2") (pintype "passive"))
      (node (ref "R24") (pin "1") (pinfunction "1_1") (pintype "passive"))
      (node (ref "SENSOR") (pin "B2") (pinfunction "VTREF_B2") (pintype "bidirectional"))
      (node (ref "U3") (pin "4") (pinfunction "OUT_4") (pintype "power_in"))
    )
    (net (code "258") (name "VTSIG") (class "Default")
      (node (ref "C66") (pin "1") (pinfunction "1_1") (pintype "passive"))
      (node (ref "R24") (pin "2") (pinfunction "2_2") (pintype "passive"))
      (node (ref "SENSOR") (pin "C2") (pinfunction "VTSIG_C2") (pintype "bidirectional"))
    )
    (net (code "259") (name "unconnected-(U1-NC-Pad2)") (class "Default")
      (node (ref "U1") (pin "2") (pinfunction "NC_2") (pintype "no_connect"))
    )
    (net (code "260") (name "unconnected-(U1-NC-Pad4)") (class "Default")
      (node (ref "U1") (pin "4") (pinfunction "NC_4") (pintype "no_connect"))
    )
    (net (code "261") (name "unconnected-(U1-NC-Pad5)") (class "Default")
      (node (ref "U1") (pin "5") (pinfunction "NC_5") (pintype "no_connect"))
    )
    (net (code "262") (name "unconnected-(U2-NC-Pad2)") (class "Default")
      (node (ref "U2") (pin "2") (pinfunction "NC_2") (pintype "no_connect"))
    )
    (net (code "263") (name "unconnected-(U2-NC-Pad4)") (class "Default")
      (node (ref "U2") (pin "4") (pinfunction "NC_4") (pintype "no_connect"))
    )
    (net (code "264") (name "unconnected-(U2-NC-Pad5)") (class "Default")
      (node (ref "U2") (pin "5") (pinfunction "NC_5") (pintype "no_connect"))
    )
    (net (code "265") (name "unconnected-(U4-2B2-Pad12)") (class "Default")
      (node (ref "U4") (pin "12") (pinfunction "2B2_12") (pintype "output"))
    )
    (net (code "266") (name "unconnected-(X-NORTH-PadM1)") (class "Default")
      (node (ref "X-NORTH") (pin "M1") (pinfunction "M1_M1") (pintype "bidirectional"))
    )
    (net (code "267") (name "unconnected-(X-NORTH-PadM2)") (class "Default")
      (node (ref "X-NORTH") (pin "M2") (pinfunction "M2_M2") (pintype "bidirectional"))
    )
    (net (code "268") (name "unconnected-(X-SOUTH-PadM1)") (class "Default")
      (node (ref "X-SOUTH") (pin "M1") (pinfunction "M1_M1") (pintype "bidirectional"))
    )
    (net (code "269") (name "unconnected-(X-SOUTH-PadM2)") (class "Default")
      (node (ref "X-SOUTH") (pin "M2") (pinfunction "M2_M2") (pintype "bidirectional"))
    )
  )
)
